# C10450-01.net
KiCad netlist of a schematic drawn in EAGLE
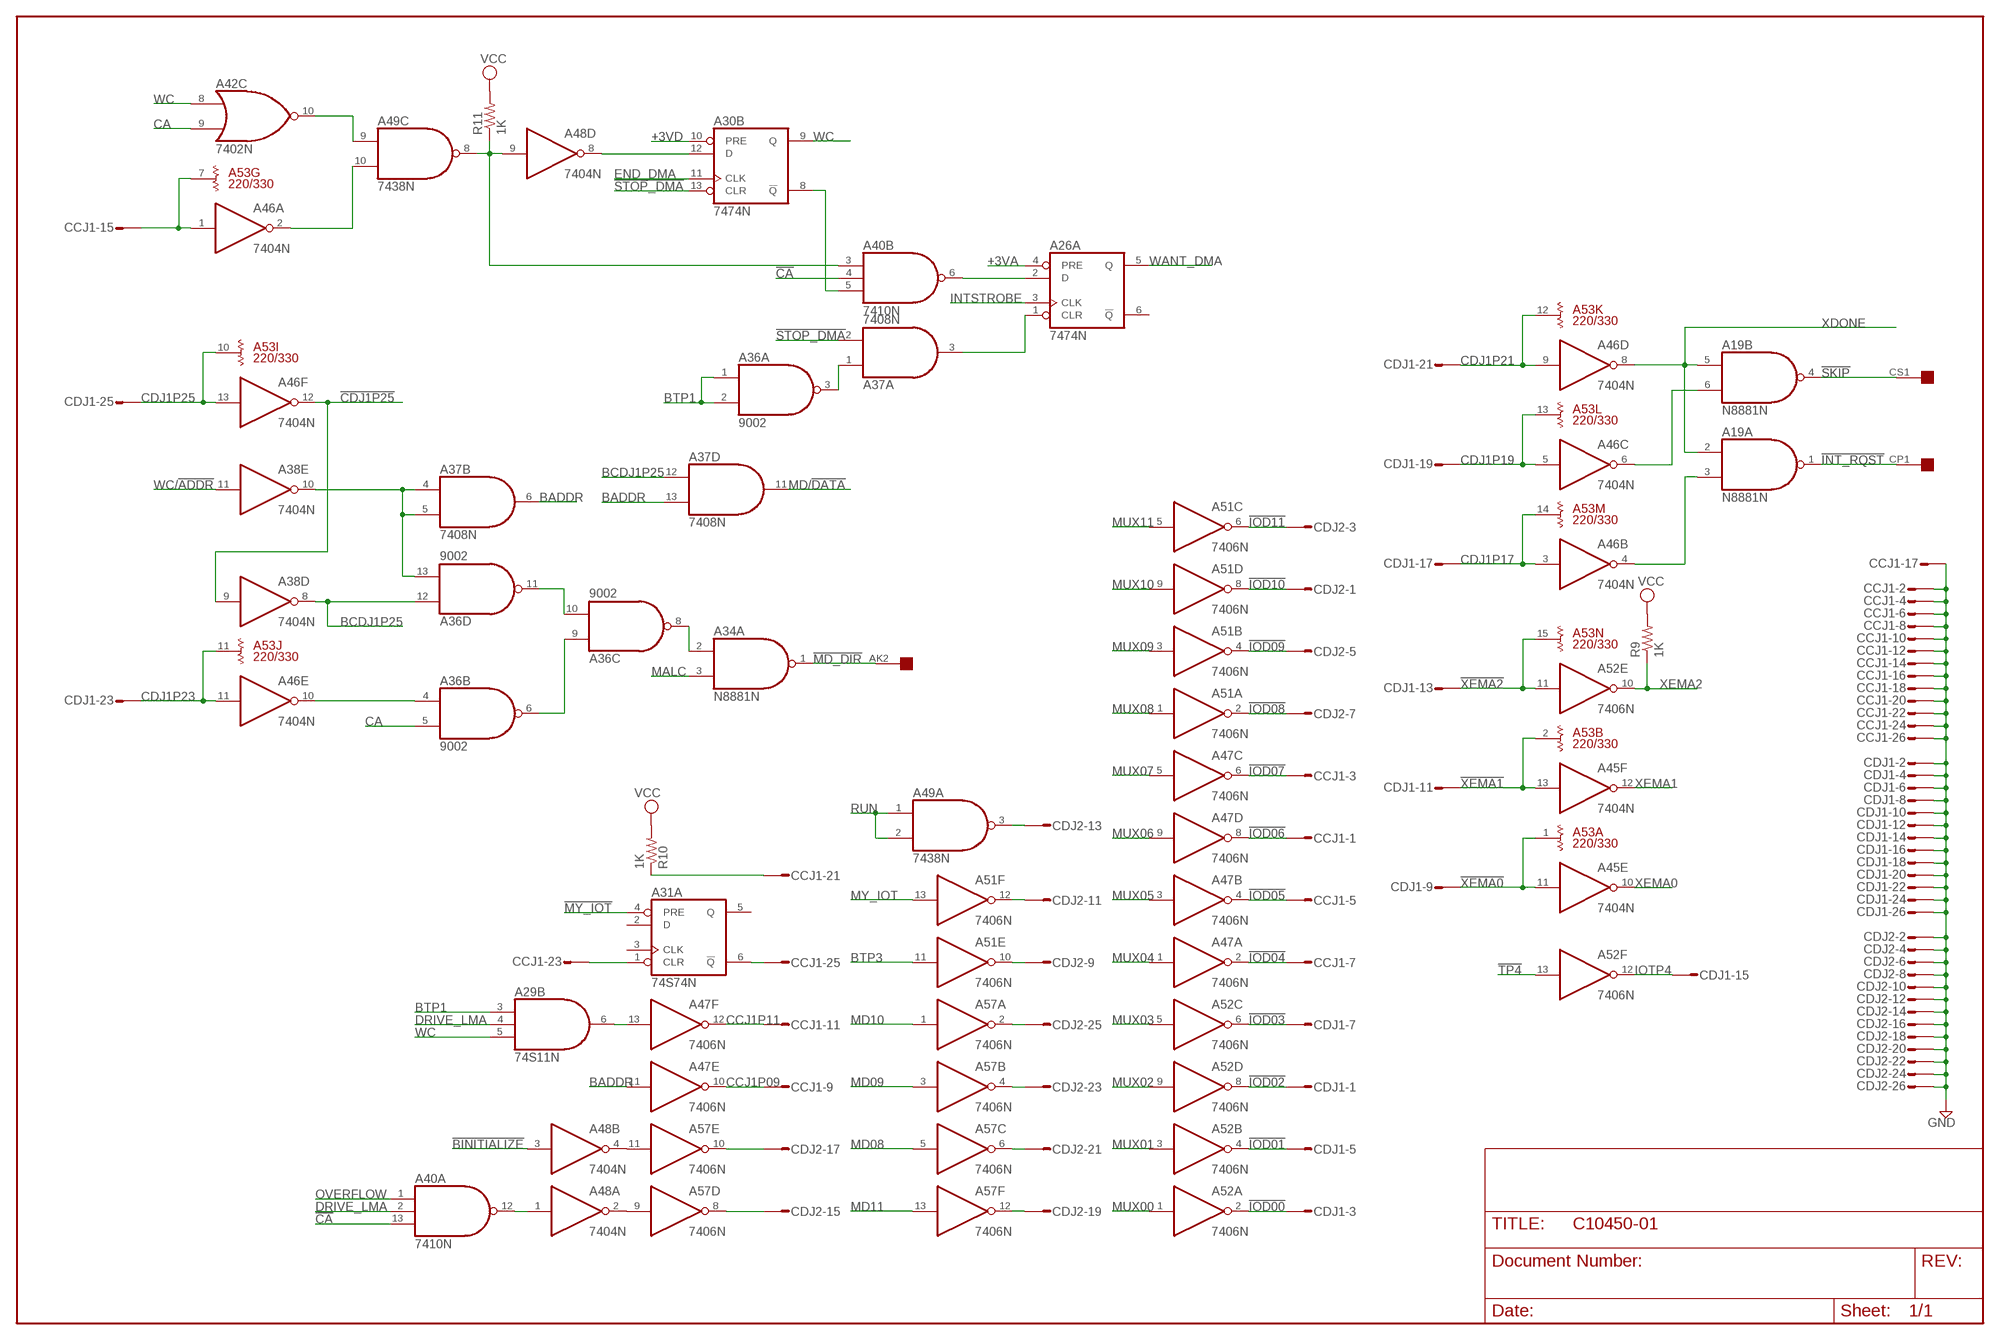
[diagram p0: schematic, sheet 1, part 1 of 3]
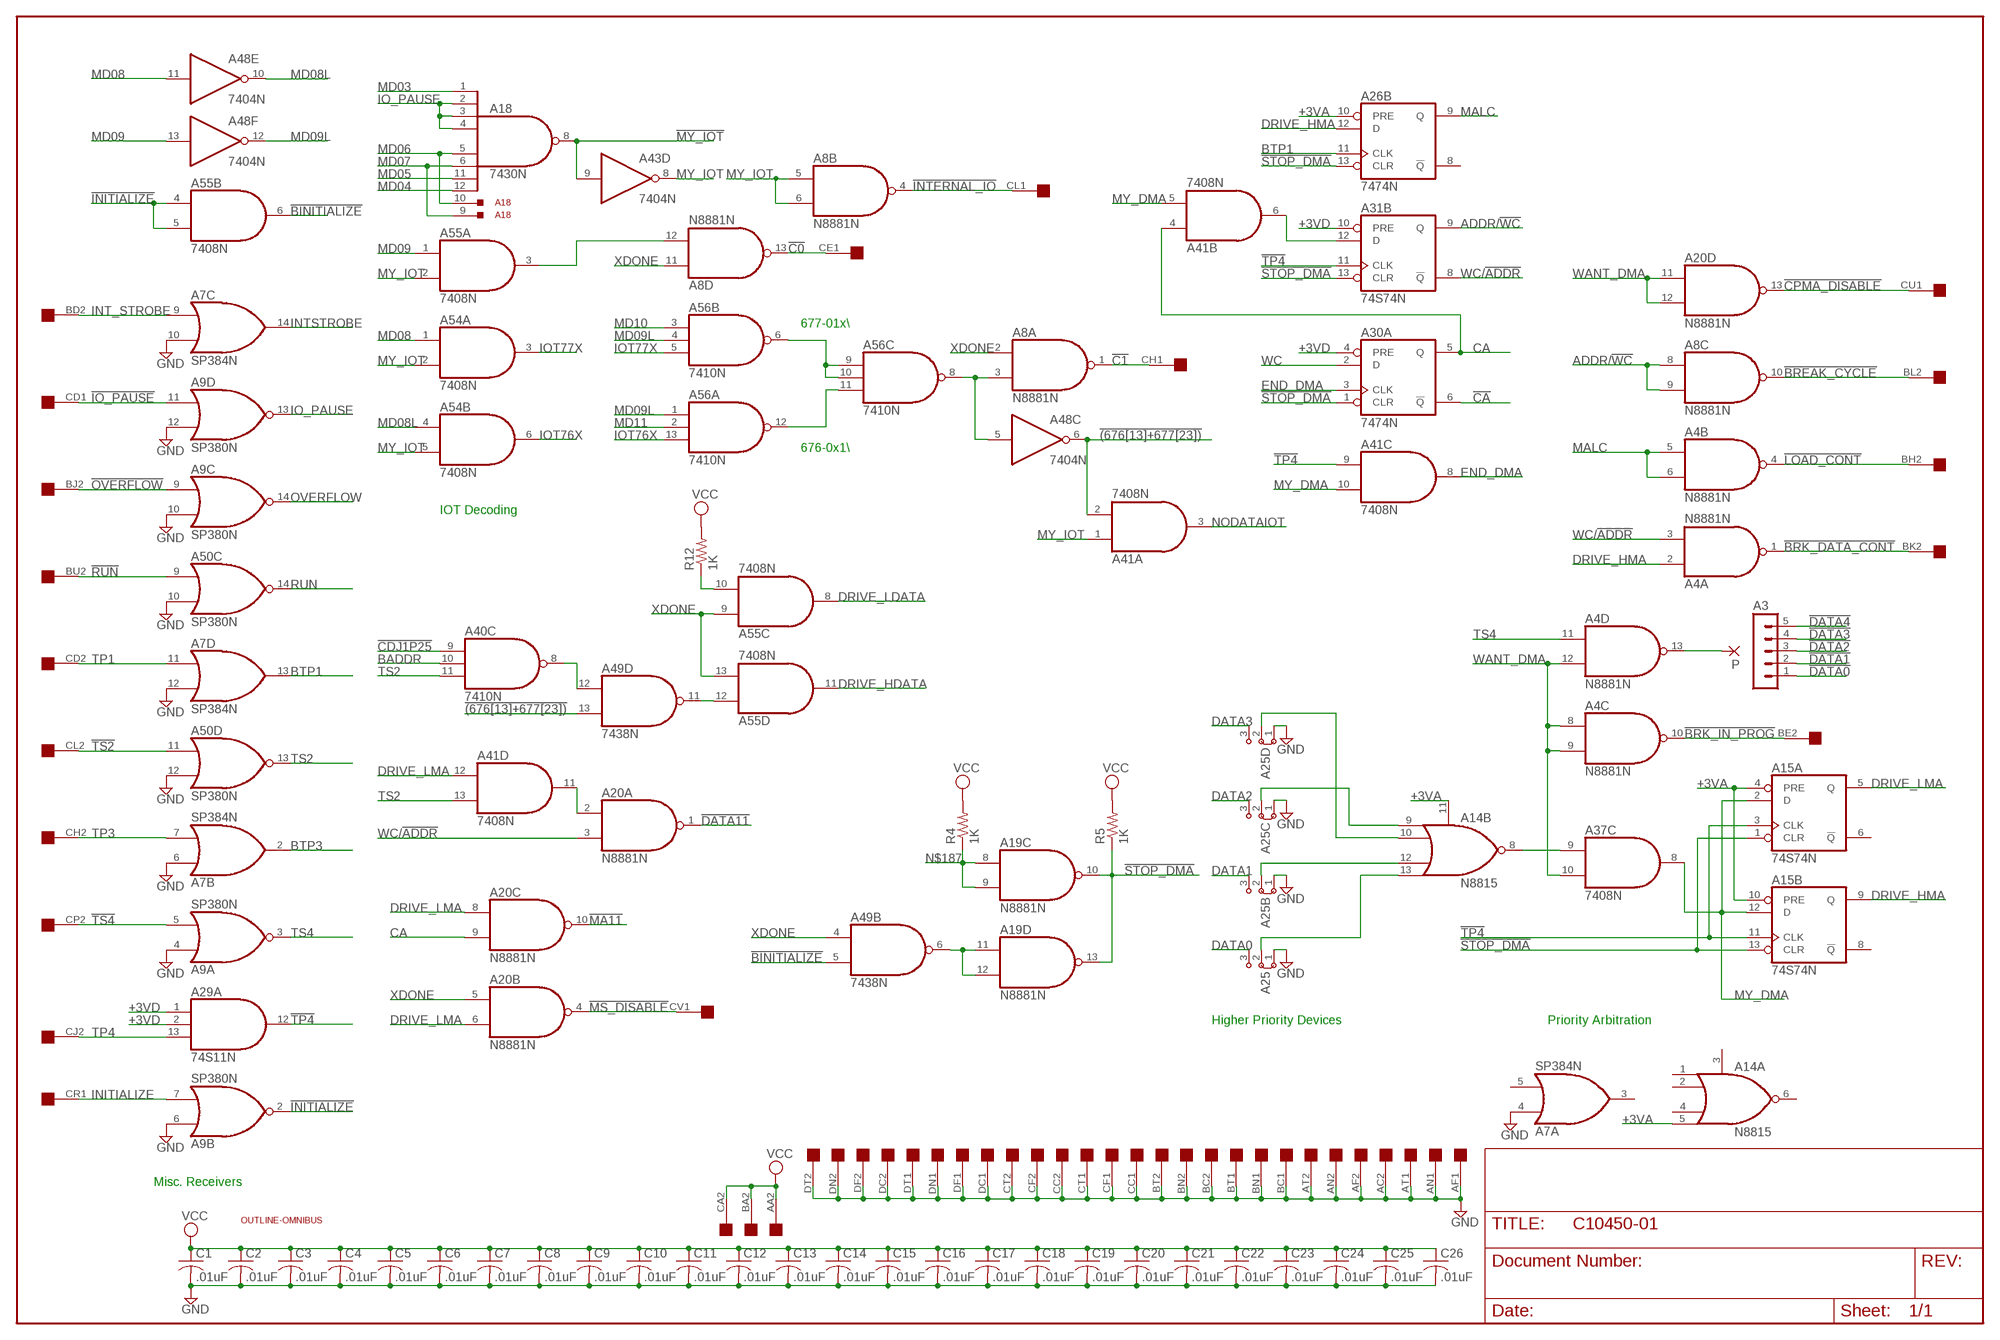
[diagram p1: schematic, sheet 1, part 2 of 3]
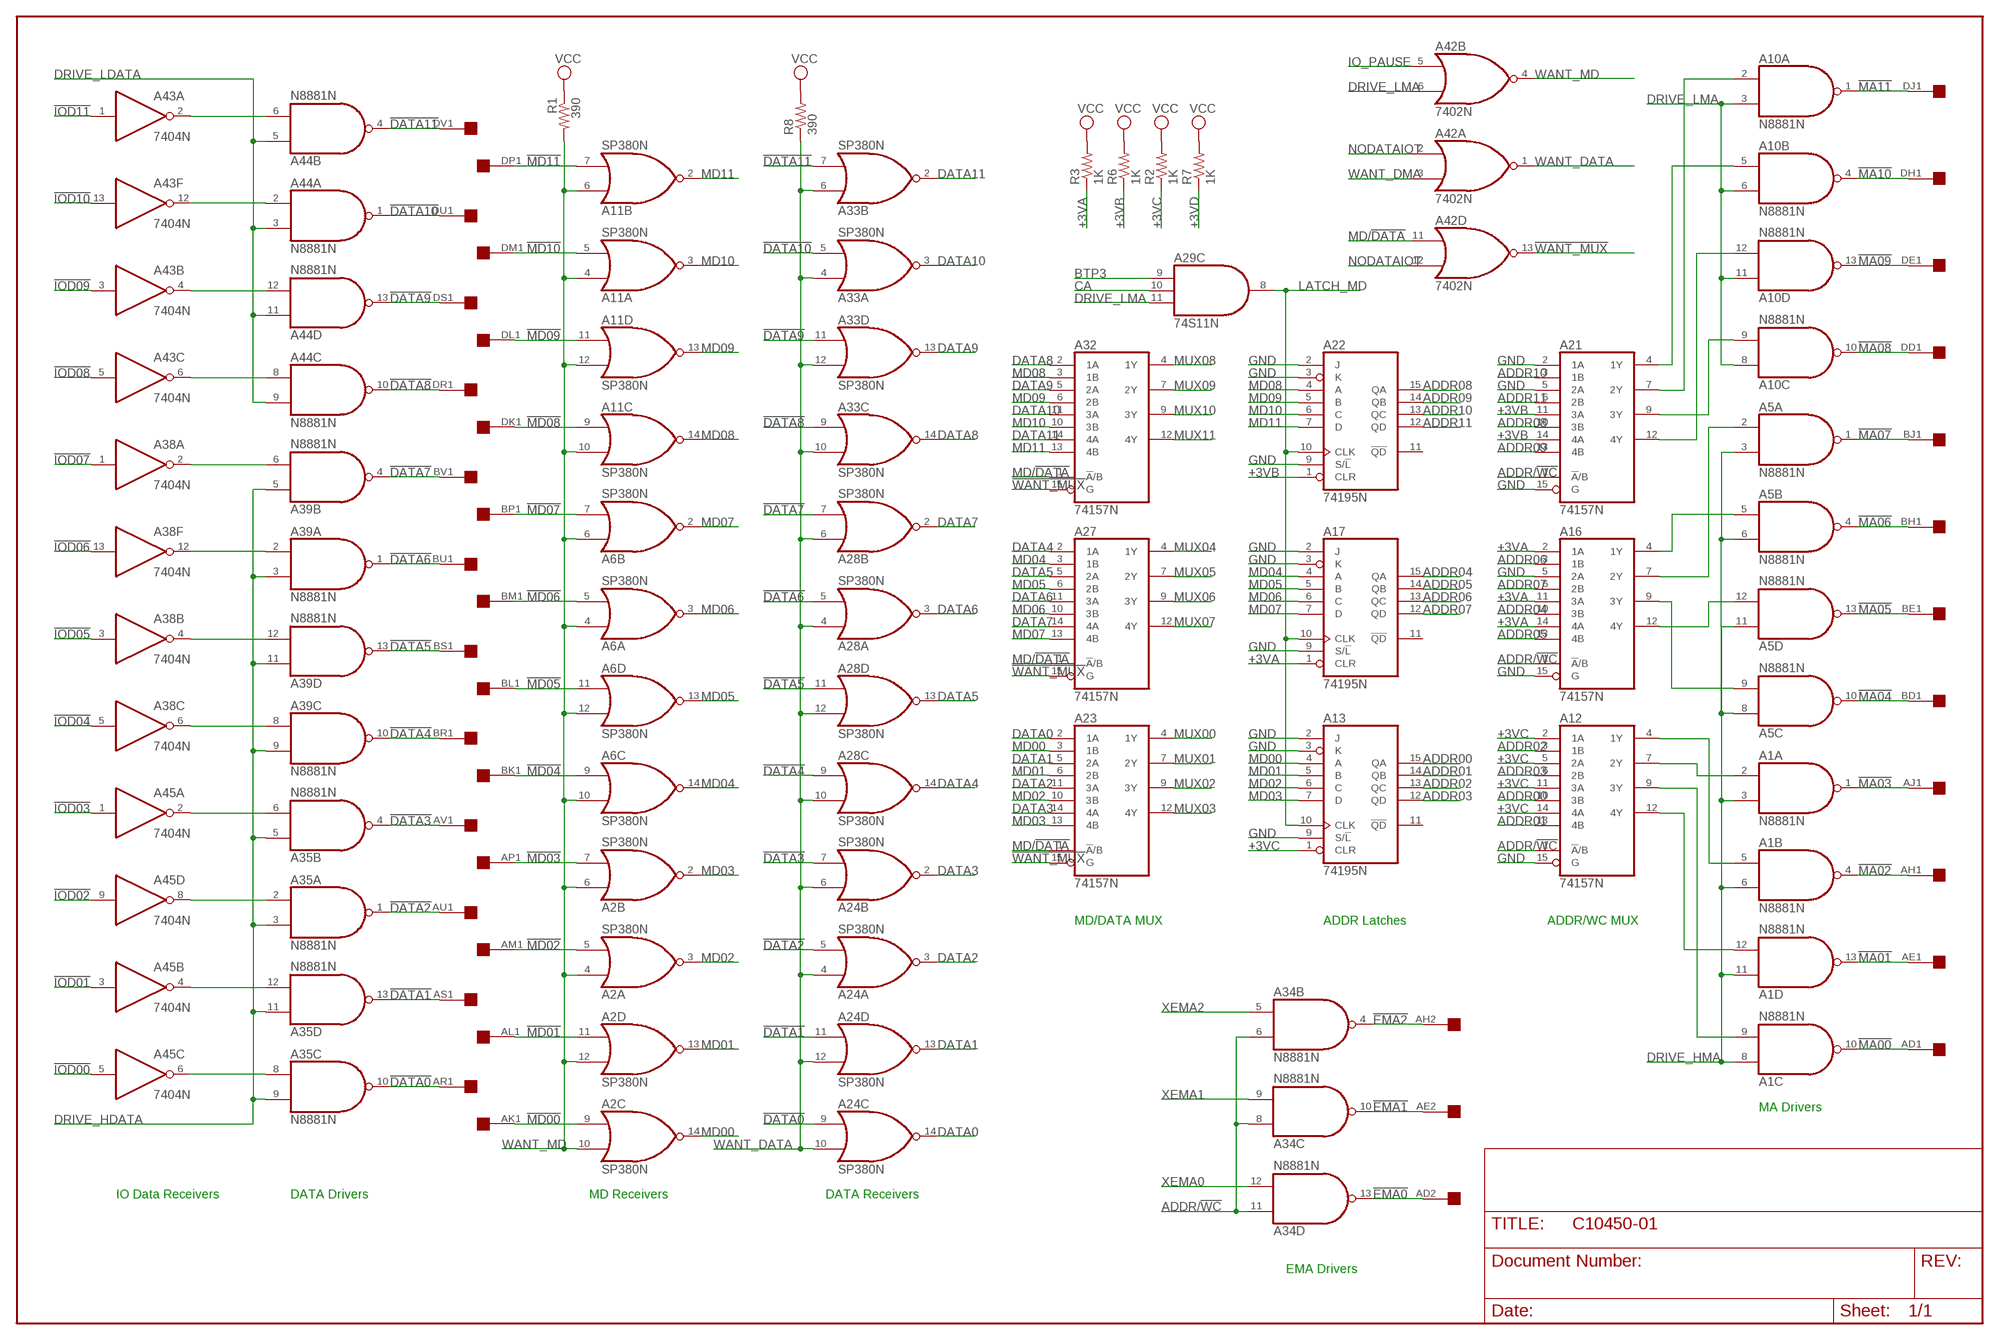
[diagram p2: schematic, sheet 1, part 3 of 3]

(export (version "E")
  (design (tool "Eeschema 10.0.6"))
  (components
    (comp (ref "A1")
      (value "N8881N")
      (footprint "eagle-import:DIL14")
      (libsource (lib "eagle-import") (part "N8881N"))
    )
    (comp (ref "A2")
      (value "SP380N")
      (footprint "eagle-import:DIL14")
      (libsource (lib "eagle-import") (part "SP380N"))
    )
    (comp (ref "A3")
      (value "MA05-1")
      (footprint "eagle-import:MA05-1")
      (libsource (lib "eagle-import") (part "MA05-1"))
    )
    (comp (ref "A4")
      (value "N8881N")
      (footprint "eagle-import:DIL14")
      (libsource (lib "eagle-import") (part "N8881N"))
    )
    (comp (ref "A5")
      (value "N8881N")
      (footprint "eagle-import:DIL14")
      (libsource (lib "eagle-import") (part "N8881N"))
    )
    (comp (ref "A6")
      (value "SP380N")
      (footprint "eagle-import:DIL14")
      (libsource (lib "eagle-import") (part "SP380N"))
    )
    (comp (ref "A7")
      (value "SP384N")
      (footprint "eagle-import:DIL14")
      (libsource (lib "eagle-import") (part "SP384N"))
    )
    (comp (ref "A8")
      (value "N8881N")
      (footprint "eagle-import:DIL14")
      (libsource (lib "eagle-import") (part "N8881N"))
    )
    (comp (ref "A9")
      (value "SP380N")
      (footprint "eagle-import:DIL14")
      (libsource (lib "eagle-import") (part "SP380N"))
    )
    (comp (ref "A10")
      (value "N8881N")
      (footprint "eagle-import:DIL14")
      (libsource (lib "eagle-import") (part "N8881N"))
    )
    (comp (ref "A11")
      (value "SP380N")
      (footprint "eagle-import:DIL14")
      (libsource (lib "eagle-import") (part "SP380N"))
    )
    (comp (ref "A12")
      (value "74157N")
      (footprint "eagle-import:DIL16")
      (libsource (lib "eagle-import") (part "74157N"))
    )
    (comp (ref "A13")
      (value "74195N")
      (footprint "eagle-import:DIL16")
      (libsource (lib "eagle-import") (part "74195NS"))
    )
    (comp (ref "A14")
      (value "N8815")
      (footprint "eagle-import:DIL14")
      (libsource (lib "eagle-import") (part "7425N"))
    )
    (comp (ref "A15")
      (value "74S74N")
      (footprint "eagle-import:DIL14")
      (libsource (lib "eagle-import") (part "7474NS"))
    )
    (comp (ref "A16")
      (value "74157N")
      (footprint "eagle-import:DIL16")
      (libsource (lib "eagle-import") (part "74157N"))
    )
    (comp (ref "A17")
      (value "74195N")
      (footprint "eagle-import:DIL16")
      (libsource (lib "eagle-import") (part "74195NS"))
    )
    (comp (ref "A18")
      (value "7430N")
      (footprint "eagle-import:DIL14")
      (libsource (lib "eagle-import") (part "7430N"))
    )
    (comp (ref "A19")
      (value "N8881N")
      (footprint "eagle-import:DIL14")
      (libsource (lib "eagle-import") (part "N8881N"))
    )
    (comp (ref "A20")
      (value "N8881N")
      (footprint "eagle-import:DIL14")
      (libsource (lib "eagle-import") (part "N8881N"))
    )
    (comp (ref "A21")
      (value "74157N")
      (footprint "eagle-import:DIL16")
      (libsource (lib "eagle-import") (part "74157N"))
    )
    (comp (ref "A22")
      (value "74195N")
      (footprint "eagle-import:DIL16")
      (libsource (lib "eagle-import") (part "74195NS"))
    )
    (comp (ref "A23")
      (value "74157N")
      (footprint "eagle-import:DIL16")
      (libsource (lib "eagle-import") (part "74157N"))
    )
    (comp (ref "A24")
      (value "SP380N")
      (footprint "eagle-import:DIL14")
      (libsource (lib "eagle-import") (part "SP380N"))
    )
    (comp (ref "A25")
      (value "J2X5MM")
      (footprint "eagle-import:05C")
      (libsource (lib "eagle-import") (part "J2X5MM"))
    )
    (comp (ref "A25B")
      (value "J2X5MM")
      (footprint "eagle-import:05C")
      (libsource (lib "eagle-import") (part "J2X5MM"))
    )
    (comp (ref "A25C")
      (value "J2X5MM")
      (footprint "eagle-import:05C")
      (libsource (lib "eagle-import") (part "J2X5MM"))
    )
    (comp (ref "A25D")
      (value "J2X5MM")
      (footprint "eagle-import:05C")
      (libsource (lib "eagle-import") (part "J2X5MM"))
    )
    (comp (ref "A26")
      (value "7474N")
      (footprint "eagle-import:DIL14")
      (libsource (lib "eagle-import") (part "7474NS"))
    )
    (comp (ref "A27")
      (value "74157N")
      (footprint "eagle-import:DIL16")
      (libsource (lib "eagle-import") (part "74157N"))
    )
    (comp (ref "A28")
      (value "SP380N")
      (footprint "eagle-import:DIL14")
      (libsource (lib "eagle-import") (part "SP380N"))
    )
    (comp (ref "A29")
      (value "74S11N")
      (footprint "eagle-import:DIL14")
      (libsource (lib "eagle-import") (part "7411NS"))
    )
    (comp (ref "A30")
      (value "7474N")
      (footprint "eagle-import:DIL14")
      (libsource (lib "eagle-import") (part "7474NS"))
    )
    (comp (ref "A31")
      (value "74S74N")
      (footprint "eagle-import:DIL14")
      (libsource (lib "eagle-import") (part "7474NS"))
    )
    (comp (ref "A32")
      (value "74157N")
      (footprint "eagle-import:DIL16")
      (libsource (lib "eagle-import") (part "74157N"))
    )
    (comp (ref "A33")
      (value "SP380N")
      (footprint "eagle-import:DIL14")
      (libsource (lib "eagle-import") (part "SP380N"))
    )
    (comp (ref "A34")
      (value "N8881N")
      (footprint "eagle-import:DIL14")
      (libsource (lib "eagle-import") (part "N8881N"))
    )
    (comp (ref "A35")
      (value "N8881N")
      (footprint "eagle-import:DIL14")
      (libsource (lib "eagle-import") (part "N8881N"))
    )
    (comp (ref "A36")
      (value "9002")
      (footprint "eagle-import:DIL14")
      (libsource (lib "eagle-import") (part "7400N"))
    )
    (comp (ref "A37")
      (value "7408N")
      (footprint "eagle-import:DIL14")
      (libsource (lib "eagle-import") (part "7408NLS"))
    )
    (comp (ref "A38")
      (value "7404N")
      (footprint "eagle-import:DIL14")
      (libsource (lib "eagle-import") (part "7404N"))
    )
    (comp (ref "A39")
      (value "N8881N")
      (footprint "eagle-import:DIL14")
      (libsource (lib "eagle-import") (part "N8881N"))
    )
    (comp (ref "A40")
      (value "7410N")
      (footprint "eagle-import:DIL14")
      (libsource (lib "eagle-import") (part "7410N"))
    )
    (comp (ref "A41")
      (value "7408N")
      (footprint "eagle-import:DIL14")
      (libsource (lib "eagle-import") (part "7408NLS"))
    )
    (comp (ref "A42")
      (value "7402N")
      (footprint "eagle-import:DIL14")
      (libsource (lib "eagle-import") (part "7402N"))
    )
    (comp (ref "A43")
      (value "7404N")
      (footprint "eagle-import:DIL14")
      (libsource (lib "eagle-import") (part "7404N"))
    )
    (comp (ref "A44")
      (value "N8881N")
      (footprint "eagle-import:DIL14")
      (libsource (lib "eagle-import") (part "N8881N"))
    )
    (comp (ref "A45")
      (value "7404N")
      (footprint "eagle-import:DIL14")
      (libsource (lib "eagle-import") (part "7404N"))
    )
    (comp (ref "A46")
      (value "7404N")
      (footprint "eagle-import:DIL14")
      (libsource (lib "eagle-import") (part "7404N"))
    )
    (comp (ref "A47")
      (value "7406N")
      (footprint "eagle-import:DIL14")
      (libsource (lib "eagle-import") (part "7406N"))
    )
    (comp (ref "A48")
      (value "7404N")
      (footprint "eagle-import:DIL14")
      (libsource (lib "eagle-import") (part "7404N"))
    )
    (comp (ref "A49")
      (value "7438N")
      (footprint "eagle-import:DIL14")
      (libsource (lib "eagle-import") (part "7438N"))
    )
    (comp (ref "A50")
      (value "SP380N")
      (footprint "eagle-import:DIL14")
      (libsource (lib "eagle-import") (part "SP380N"))
    )
    (comp (ref "A51")
      (value "7406N")
      (footprint "eagle-import:DIL14")
      (libsource (lib "eagle-import") (part "7406N"))
    )
    (comp (ref "A52")
      (value "7406N")
      (footprint "eagle-import:DIL14")
      (libsource (lib "eagle-import") (part "7406N"))
    )
    (comp (ref "A53")
      (value "220/330")
      (footprint "eagle-import:DIL16")
      (libsource (lib "eagle-import") (part "220/330"))
    )
    (comp (ref "A54")
      (value "7408N")
      (footprint "eagle-import:DIL14")
      (libsource (lib "eagle-import") (part "7408NLS"))
    )
    (comp (ref "A55")
      (value "7408N")
      (footprint "eagle-import:DIL14")
      (libsource (lib "eagle-import") (part "7408NLS"))
    )
    (comp (ref "A56")
      (value "7410N")
      (footprint "eagle-import:DIL14")
      (libsource (lib "eagle-import") (part "7410N"))
    )
    (comp (ref "A57")
      (value "7406N")
      (footprint "eagle-import:DIL14")
      (libsource (lib "eagle-import") (part "7406N"))
    )
    (comp (ref "C1")
      (value ".01uF")
      (footprint "eagle-import:C050-025X075")
      (libsource (lib "eagle-import") (part "C-US050-025X075"))
    )
    (comp (ref "C2")
      (value ".01uF")
      (footprint "eagle-import:C050-025X075")
      (libsource (lib "eagle-import") (part "C-US050-025X075"))
    )
    (comp (ref "C3")
      (value ".01uF")
      (footprint "eagle-import:C050-025X075")
      (libsource (lib "eagle-import") (part "C-US050-025X075"))
    )
    (comp (ref "C4")
      (value ".01uF")
      (footprint "eagle-import:C050-025X075")
      (libsource (lib "eagle-import") (part "C-US050-025X075"))
    )
    (comp (ref "C5")
      (value ".01uF")
      (footprint "eagle-import:C050-025X075")
      (libsource (lib "eagle-import") (part "C-US050-025X075"))
    )
    (comp (ref "C6")
      (value ".01uF")
      (footprint "eagle-import:C050-025X075")
      (libsource (lib "eagle-import") (part "C-US050-025X075"))
    )
    (comp (ref "C7")
      (value ".01uF")
      (footprint "eagle-import:C050-025X075")
      (libsource (lib "eagle-import") (part "C-US050-025X075"))
    )
    (comp (ref "C8")
      (value ".01uF")
      (footprint "eagle-import:C050-025X075")
      (libsource (lib "eagle-import") (part "C-US050-025X075"))
    )
    (comp (ref "C9")
      (value ".01uF")
      (footprint "eagle-import:C050-025X075")
      (libsource (lib "eagle-import") (part "C-US050-025X075"))
    )
    (comp (ref "C10")
      (value ".01uF")
      (footprint "eagle-import:C050-025X075")
      (libsource (lib "eagle-import") (part "C-US050-025X075"))
    )
    (comp (ref "C11")
      (value ".01uF")
      (footprint "eagle-import:C050-025X075")
      (libsource (lib "eagle-import") (part "C-US050-025X075"))
    )
    (comp (ref "C12")
      (value ".01uF")
      (footprint "eagle-import:C050-025X075")
      (libsource (lib "eagle-import") (part "C-US050-025X075"))
    )
    (comp (ref "C13")
      (value ".01uF")
      (footprint "eagle-import:C050-025X075")
      (libsource (lib "eagle-import") (part "C-US050-025X075"))
    )
    (comp (ref "C14")
      (value ".01uF")
      (footprint "eagle-import:C050-025X075")
      (libsource (lib "eagle-import") (part "C-US050-025X075"))
    )
    (comp (ref "C15")
      (value ".01uF")
      (footprint "eagle-import:C050-025X075")
      (libsource (lib "eagle-import") (part "C-US050-025X075"))
    )
    (comp (ref "C16")
      (value ".01uF")
      (footprint "eagle-import:C050-025X075")
      (libsource (lib "eagle-import") (part "C-US050-025X075"))
    )
    (comp (ref "C17")
      (value ".01uF")
      (footprint "eagle-import:C050-025X075")
      (libsource (lib "eagle-import") (part "C-US050-025X075"))
    )
    (comp (ref "C18")
      (value ".01uF")
      (footprint "eagle-import:C050-025X075")
      (libsource (lib "eagle-import") (part "C-US050-025X075"))
    )
    (comp (ref "C19")
      (value ".01uF")
      (footprint "eagle-import:C050-025X075")
      (libsource (lib "eagle-import") (part "C-US050-025X075"))
    )
    (comp (ref "C20")
      (value ".01uF")
      (footprint "eagle-import:C050-025X075")
      (libsource (lib "eagle-import") (part "C-US050-025X075"))
    )
    (comp (ref "C21")
      (value ".01uF")
      (footprint "eagle-import:C050-025X075")
      (libsource (lib "eagle-import") (part "C-US050-025X075"))
    )
    (comp (ref "C22")
      (value ".01uF")
      (footprint "eagle-import:C050-025X075")
      (libsource (lib "eagle-import") (part "C-US050-025X075"))
    )
    (comp (ref "C23")
      (value ".01uF")
      (footprint "eagle-import:C050-025X075")
      (libsource (lib "eagle-import") (part "C-US050-025X075"))
    )
    (comp (ref "C24")
      (value ".01uF")
      (footprint "eagle-import:C050-025X075")
      (libsource (lib "eagle-import") (part "C-US050-025X075"))
    )
    (comp (ref "C25")
      (value ".01uF")
      (footprint "eagle-import:C050-025X075")
      (libsource (lib "eagle-import") (part "C-US050-025X075"))
    )
    (comp (ref "C26")
      (value ".01uF")
      (footprint "eagle-import:C050-025X075")
      (libsource (lib "eagle-import") (part "C-US050-025X075"))
    )
    (comp (ref "CCJ1")
      (value "26HS")
      (footprint "eagle-import:26H")
      (libsource (lib "eagle-import") (part "26HS"))
    )
    (comp (ref "CDJ1")
      (value "26HS")
      (footprint "eagle-import:26H")
      (libsource (lib "eagle-import") (part "26HS"))
    )
    (comp (ref "CDJ2")
      (value "26HS")
      (footprint "eagle-import:26H")
      (libsource (lib "eagle-import") (part "26HS"))
    )
    (comp (ref "P")
      (value "1,6/0,8")
      (footprint "eagle-import:1,6_0,8")
      (libsource (lib "eagle-import") (part "1,6/0,8"))
    )
    (comp (ref "R1")
      (value "390")
      (footprint "eagle-import:0207_10")
      (libsource (lib "eagle-import") (part "R-US_0207/10"))
    )
    (comp (ref "R2")
      (value "1K")
      (footprint "eagle-import:0207_10")
      (libsource (lib "eagle-import") (part "R-US_0207/10"))
    )
    (comp (ref "R3")
      (value "1K")
      (footprint "eagle-import:0207_10")
      (libsource (lib "eagle-import") (part "R-US_0207/10"))
    )
    (comp (ref "R4")
      (value "1K")
      (footprint "eagle-import:0207_10")
      (libsource (lib "eagle-import") (part "R-US_0207/10"))
    )
    (comp (ref "R5")
      (value "1K")
      (footprint "eagle-import:0207_10")
      (libsource (lib "eagle-import") (part "R-US_0207/10"))
    )
    (comp (ref "R6")
      (value "1K")
      (footprint "eagle-import:0207_10")
      (libsource (lib "eagle-import") (part "R-US_0207/10"))
    )
    (comp (ref "R7")
      (value "1K")
      (footprint "eagle-import:0207_10")
      (libsource (lib "eagle-import") (part "R-US_0207/10"))
    )
    (comp (ref "R8")
      (value "390")
      (footprint "eagle-import:0207_10")
      (libsource (lib "eagle-import") (part "R-US_0207/10"))
    )
    (comp (ref "R9")
      (value "1K")
      (footprint "eagle-import:0207_10")
      (libsource (lib "eagle-import") (part "R-US_0207/10"))
    )
    (comp (ref "R10")
      (value "1K")
      (footprint "eagle-import:0207_10")
      (libsource (lib "eagle-import") (part "R-US_0207/10"))
    )
    (comp (ref "R11")
      (value "1K")
      (footprint "eagle-import:0207_10")
      (libsource (lib "eagle-import") (part "R-US_0207/10"))
    )
    (comp (ref "R12")
      (value "1K")
      (footprint "eagle-import:0207_10")
      (libsource (lib "eagle-import") (part "R-US_0207/10"))
    )
    (comp (ref "U$1")
      (value "OUTLINE-OMNIBUS")
      (footprint "eagle-import:OMNIBUS")
      (libsource (lib "eagle-import") (part "OUTLINE-OMNIBUS"))
    )
    (comp (ref "U$2")
      (value "QUAD")
      (footprint "eagle-import:EDGE-CON8")
      (libsource (lib "eagle-import") (part "QUAD"))
    )
  )
  (nets
    (net (code "1") (name "/+3VA") (class "Default")
      (node (ref "A14") (pin "11") (pinfunction "G_11") (pintype "input"))
      (node (ref "A14") (pin "5") (pinfunction "I3_5") (pintype "input"))
      (node (ref "A15") (pin "10") (pinfunction "PRE_10") (pintype "input"))
      (node (ref "A15") (pin "4") (pinfunction "PRE_4") (pintype "input"))
      (node (ref "A16") (pin "11") (pinfunction "3A_11") (pintype "input"))
      (node (ref "A16") (pin "14") (pinfunction "4A_14") (pintype "input"))
      (node (ref "A16") (pin "2") (pinfunction "1A_2") (pintype "input"))
      (node (ref "A17") (pin "1") (pinfunction "CLR_1") (pintype "input"))
      (node (ref "A26") (pin "10") (pinfunction "PRE_10") (pintype "input"))
      (node (ref "A26") (pin "4") (pinfunction "PRE_4") (pintype "input"))
      (node (ref "R3") (pin "1") (pinfunction "1_1") (pintype "passive"))
    )
    (net (code "2") (name "/+3VB") (class "Default")
      (node (ref "A21") (pin "11") (pinfunction "3A_11") (pintype "input"))
      (node (ref "A21") (pin "14") (pinfunction "4A_14") (pintype "input"))
      (node (ref "A22") (pin "1") (pinfunction "CLR_1") (pintype "input"))
      (node (ref "R6") (pin "1") (pinfunction "1_1") (pintype "passive"))
    )
    (net (code "3") (name "/+3VC") (class "Default")
      (node (ref "A12") (pin "11") (pinfunction "3A_11") (pintype "input"))
      (node (ref "A12") (pin "14") (pinfunction "4A_14") (pintype "input"))
      (node (ref "A12") (pin "2") (pinfunction "1A_2") (pintype "input"))
      (node (ref "A12") (pin "5") (pinfunction "2A_5") (pintype "input"))
      (node (ref "A13") (pin "1") (pinfunction "CLR_1") (pintype "input"))
      (node (ref "R2") (pin "1") (pinfunction "1_1") (pintype "passive"))
    )
    (net (code "4") (name "/+3VD") (class "Default")
      (node (ref "A29") (pin "1") (pinfunction "I0_1") (pintype "input"))
      (node (ref "A29") (pin "2") (pinfunction "I1_2") (pintype "input"))
      (node (ref "A30") (pin "10") (pinfunction "PRE_10") (pintype "input"))
      (node (ref "A30") (pin "4") (pinfunction "PRE_4") (pintype "input"))
      (node (ref "A31") (pin "10") (pinfunction "PRE_10") (pintype "input"))
      (node (ref "R7") (pin "1") (pinfunction "1_1") (pintype "passive"))
    )
    (net (code "5") (name "/ADDR00") (class "Default")
      (node (ref "A12") (pin "10") (pinfunction "3B_10") (pintype "input"))
      (node (ref "A13") (pin "15") (pinfunction "QA_15") (pintype "output"))
    )
    (net (code "6") (name "/ADDR01") (class "Default")
      (node (ref "A12") (pin "13") (pinfunction "4B_13") (pintype "input"))
      (node (ref "A13") (pin "14") (pinfunction "QB_14") (pintype "output"))
    )
    (net (code "7") (name "/ADDR02") (class "Default")
      (node (ref "A12") (pin "3") (pinfunction "1B_3") (pintype "input"))
      (node (ref "A13") (pin "13") (pinfunction "QC_13") (pintype "output"))
    )
    (net (code "8") (name "/ADDR03") (class "Default")
      (node (ref "A12") (pin "6") (pinfunction "2B_6") (pintype "input"))
      (node (ref "A13") (pin "12") (pinfunction "QD_12") (pintype "output"))
    )
    (net (code "9") (name "/ADDR04") (class "Default")
      (node (ref "A16") (pin "10") (pinfunction "3B_10") (pintype "input"))
      (node (ref "A17") (pin "15") (pinfunction "QA_15") (pintype "output"))
    )
    (net (code "10") (name "/ADDR05") (class "Default")
      (node (ref "A16") (pin "13") (pinfunction "4B_13") (pintype "input"))
      (node (ref "A17") (pin "14") (pinfunction "QB_14") (pintype "output"))
    )
    (net (code "11") (name "/ADDR06") (class "Default")
      (node (ref "A16") (pin "3") (pinfunction "1B_3") (pintype "input"))
      (node (ref "A17") (pin "13") (pinfunction "QC_13") (pintype "output"))
    )
    (net (code "12") (name "/ADDR07") (class "Default")
      (node (ref "A16") (pin "6") (pinfunction "2B_6") (pintype "input"))
      (node (ref "A17") (pin "12") (pinfunction "QD_12") (pintype "output"))
    )
    (net (code "13") (name "/ADDR08") (class "Default")
      (node (ref "A21") (pin "10") (pinfunction "3B_10") (pintype "input"))
      (node (ref "A22") (pin "15") (pinfunction "QA_15") (pintype "output"))
    )
    (net (code "14") (name "/ADDR09") (class "Default")
      (node (ref "A21") (pin "13") (pinfunction "4B_13") (pintype "input"))
      (node (ref "A22") (pin "14") (pinfunction "QB_14") (pintype "output"))
    )
    (net (code "15") (name "/ADDR10") (class "Default")
      (node (ref "A21") (pin "3") (pinfunction "1B_3") (pintype "input"))
      (node (ref "A22") (pin "13") (pinfunction "QC_13") (pintype "output"))
    )
    (net (code "16") (name "/ADDR11") (class "Default")
      (node (ref "A21") (pin "6") (pinfunction "2B_6") (pintype "input"))
      (node (ref "A22") (pin "12") (pinfunction "QD_12") (pintype "output"))
    )
    (net (code "17") (name "/ADDR{slash}~{WC}") (class "Default")
      (node (ref "A12") (pin "1") (pinfunction "~{A}/B_1") (pintype "input"))
      (node (ref "A16") (pin "1") (pinfunction "~{A}/B_1") (pintype "input"))
      (node (ref "A21") (pin "1") (pinfunction "~{A}/B_1") (pintype "input"))
      (node (ref "A31") (pin "9") (pinfunction "Q_9") (pintype "output"))
      (node (ref "A34") (pin "11") (pinfunction "I0_11") (pintype "input"))
      (node (ref "A34") (pin "6") (pinfunction "I1_6") (pintype "input"))
      (node (ref "A34") (pin "8") (pinfunction "I0_8") (pintype "input"))
      (node (ref "A8") (pin "8") (pinfunction "I0_8") (pintype "input"))
      (node (ref "A8") (pin "9") (pinfunction "I1_9") (pintype "input"))
    )
    (net (code "18") (name "/BADDR") (class "Default")
      (node (ref "A37") (pin "13") (pinfunction "I1_13") (pintype "input"))
      (node (ref "A37") (pin "6") (pinfunction "O_6") (pintype "output"))
      (node (ref "A40") (pin "10") (pinfunction "I1_10") (pintype "input"))
      (node (ref "A47") (pin "11") (pinfunction "I_11") (pintype "input"))
    )
    (net (code "19") (name "/BCDJ1P25") (class "Default")
      (node (ref "A36") (pin "12") (pinfunction "I0_12") (pintype "input"))
      (node (ref "A37") (pin "12") (pinfunction "I0_12") (pintype "input"))
      (node (ref "A38") (pin "8") (pinfunction "O_8") (pintype "output"))
    )
    (net (code "20") (name "/BTP1") (class "Default")
      (node (ref "A26") (pin "11") (pinfunction "CLK_11") (pintype "input"))
      (node (ref "A29") (pin "3") (pinfunction "I0_3") (pintype "input"))
      (node (ref "A36") (pin "1") (pinfunction "I0_1") (pintype "input"))
      (node (ref "A36") (pin "2") (pinfunction "I1_2") (pintype "input"))
      (node (ref "A7") (pin "13") (pinfunction "O_13") (pintype "output"))
    )
    (net (code "21") (name "/BTP3") (class "Default")
      (node (ref "A29") (pin "9") (pinfunction "I0_9") (pintype "input"))
      (node (ref "A51") (pin "11") (pinfunction "I_11") (pintype "input"))
      (node (ref "A7") (pin "2") (pinfunction "O_2") (pintype "output"))
    )
    (net (code "22") (name "/CA") (class "Default")
      (node (ref "A20") (pin "9") (pinfunction "I1_9") (pintype "input"))
      (node (ref "A29") (pin "10") (pinfunction "I1_10") (pintype "input"))
      (node (ref "A30") (pin "5") (pinfunction "Q_5") (pintype "output"))
      (node (ref "A36") (pin "5") (pinfunction "I1_5") (pintype "input"))
      (node (ref "A41") (pin "4") (pinfunction "I0_4") (pintype "input"))
      (node (ref "A42") (pin "9") (pinfunction "I1_9") (pintype "input"))
    )
    (net (code "23") (name "/CCJ1P09") (class "Default")
      (node (ref "A47") (pin "10") (pinfunction "O_10") (pintype "open_collector"))
      (node (ref "CCJ1") (pin "9") (pinfunction "S_9") (pintype "passive"))
    )
    (net (code "24") (name "/CCJ1P11") (class "Default")
      (node (ref "A47") (pin "12") (pinfunction "O_12") (pintype "open_collector"))
      (node (ref "CCJ1") (pin "11") (pinfunction "S_11") (pintype "passive"))
    )
    (net (code "25") (name "/CDJ1P17") (class "Default")
      (node (ref "A46") (pin "3") (pinfunction "I_3") (pintype "input"))
      (node (ref "A53") (pin "14") (pinfunction "TERM_14") (pintype "input"))
      (node (ref "CDJ1") (pin "17") (pinfunction "S_17") (pintype "passive"))
    )
    (net (code "26") (name "/CDJ1P19") (class "Default")
      (node (ref "A46") (pin "5") (pinfunction "I_5") (pintype "input"))
      (node (ref "A53") (pin "13") (pinfunction "TERM_13") (pintype "input"))
      (node (ref "CDJ1") (pin "19") (pinfunction "S_19") (pintype "passive"))
    )
    (net (code "27") (name "/CDJ1P21") (class "Default")
      (node (ref "A46") (pin "9") (pinfunction "I_9") (pintype "input"))
      (node (ref "A53") (pin "12") (pinfunction "TERM_12") (pintype "input"))
      (node (ref "CDJ1") (pin "21") (pinfunction "S_21") (pintype "passive"))
    )
    (net (code "28") (name "/CDJ1P23") (class "Default")
      (node (ref "A46") (pin "11") (pinfunction "I_11") (pintype "input"))
      (node (ref "A53") (pin "11") (pinfunction "TERM_11") (pintype "input"))
      (node (ref "CDJ1") (pin "23") (pinfunction "S_23") (pintype "passive"))
    )
    (net (code "29") (name "/CDJ1P25") (class "Default")
      (node (ref "A46") (pin "13") (pinfunction "I_13") (pintype "input"))
      (node (ref "A53") (pin "10") (pinfunction "TERM_10") (pintype "input"))
      (node (ref "CDJ1") (pin "25") (pinfunction "S_25") (pintype "passive"))
    )
    (net (code "30") (name "/DATA0") (class "Default")
      (node (ref "A23") (pin "2") (pinfunction "1A_2") (pintype "input"))
      (node (ref "A24") (pin "14") (pinfunction "O_14") (pintype "output"))
      (node (ref "A25") (pin "3") (pinfunction "3_3") (pintype "passive"))
    )
    (net (code "31") (name "/DATA1") (class "Default")
      (node (ref "A23") (pin "5") (pinfunction "2A_5") (pintype "input"))
      (node (ref "A24") (pin "13") (pinfunction "O_13") (pintype "output"))
      (node (ref "A25B") (pin "3") (pinfunction "3_3") (pintype "passive"))
    )
    (net (code "32") (name "/DATA2") (class "Default")
      (node (ref "A23") (pin "11") (pinfunction "3A_11") (pintype "input"))
      (node (ref "A24") (pin "3") (pinfunction "O_3") (pintype "output"))
      (node (ref "A25C") (pin "3") (pinfunction "3_3") (pintype "passive"))
    )
    (net (code "33") (name "/DATA3") (class "Default")
      (node (ref "A23") (pin "14") (pinfunction "4A_14") (pintype "input"))
      (node (ref "A24") (pin "2") (pinfunction "O_2") (pintype "output"))
      (node (ref "A25D") (pin "3") (pinfunction "3_3") (pintype "passive"))
    )
    (net (code "34") (name "/DATA4") (class "Default")
      (node (ref "A27") (pin "2") (pinfunction "1A_2") (pintype "input"))
      (node (ref "A28") (pin "14") (pinfunction "O_14") (pintype "output"))
    )
    (net (code "35") (name "/DATA5") (class "Default")
      (node (ref "A27") (pin "5") (pinfunction "2A_5") (pintype "input"))
      (node (ref "A28") (pin "13") (pinfunction "O_13") (pintype "output"))
    )
    (net (code "36") (name "/DATA6") (class "Default")
      (node (ref "A27") (pin "11") (pinfunction "3A_11") (pintype "input"))
      (node (ref "A28") (pin "3") (pinfunction "O_3") (pintype "output"))
    )
    (net (code "37") (name "/DATA7") (class "Default")
      (node (ref "A27") (pin "14") (pinfunction "4A_14") (pintype "input"))
      (node (ref "A28") (pin "2") (pinfunction "O_2") (pintype "output"))
    )
    (net (code "38") (name "/DATA8") (class "Default")
      (node (ref "A32") (pin "2") (pinfunction "1A_2") (pintype "input"))
      (node (ref "A33") (pin "14") (pinfunction "O_14") (pintype "output"))
    )
    (net (code "39") (name "/DATA9") (class "Default")
      (node (ref "A32") (pin "5") (pinfunction "2A_5") (pintype "input"))
      (node (ref "A33") (pin "13") (pinfunction "O_13") (pintype "output"))
    )
    (net (code "40") (name "/DATA10") (class "Default")
      (node (ref "A32") (pin "11") (pinfunction "3A_11") (pintype "input"))
      (node (ref "A33") (pin "3") (pinfunction "O_3") (pintype "output"))
    )
    (net (code "41") (name "/DATA11") (class "Default")
      (node (ref "A32") (pin "14") (pinfunction "4A_14") (pintype "input"))
      (node (ref "A33") (pin "2") (pinfunction "O_2") (pintype "output"))
    )
    (net (code "42") (name "/DRIVE_HDATA") (class "Default")
      (node (ref "A35") (pin "11") (pinfunction "I0_11") (pintype "input"))
      (node (ref "A35") (pin "3") (pinfunction "I1_3") (pintype "input"))
      (node (ref "A35") (pin "5") (pinfunction "I0_5") (pintype "input"))
      (node (ref "A35") (pin "9") (pinfunction "I1_9") (pintype "input"))
      (node (ref "A39") (pin "11") (pinfunction "I0_11") (pintype "input"))
      (node (ref "A39") (pin "3") (pinfunction "I1_3") (pintype "input"))
      (node (ref "A39") (pin "5") (pinfunction "I0_5") (pintype "input"))
      (node (ref "A39") (pin "9") (pinfunction "I1_9") (pintype "input"))
      (node (ref "A55") (pin "11") (pinfunction "O_11") (pintype "output"))
    )
    (net (code "43") (name "/DRIVE_HMA") (class "Default")
      (node (ref "A1") (pin "11") (pinfunction "I0_11") (pintype "input"))
      (node (ref "A1") (pin "3") (pinfunction "I1_3") (pintype "input"))
      (node (ref "A1") (pin "6") (pinfunction "I1_6") (pintype "input"))
      (node (ref "A1") (pin "8") (pinfunction "I0_8") (pintype "input"))
      (node (ref "A15") (pin "9") (pinfunction "Q_9") (pintype "output"))
      (node (ref "A26") (pin "12") (pinfunction "D_12") (pintype "input"))
      (node (ref "A4") (pin "2") (pinfunction "I0_2") (pintype "input"))
      (node (ref "A5") (pin "11") (pinfunction "I0_11") (pintype "input"))
      (node (ref "A5") (pin "3") (pinfunction "I1_3") (pintype "input"))
      (node (ref "A5") (pin "6") (pinfunction "I1_6") (pintype "input"))
      (node (ref "A5") (pin "8") (pinfunction "I0_8") (pintype "input"))
    )
    (net (code "44") (name "/DRIVE_LDATA") (class "Default")
      (node (ref "A44") (pin "11") (pinfunction "I0_11") (pintype "input"))
      (node (ref "A44") (pin "3") (pinfunction "I1_3") (pintype "input"))
      (node (ref "A44") (pin "5") (pinfunction "I0_5") (pintype "input"))
      (node (ref "A44") (pin "9") (pinfunction "I1_9") (pintype "input"))
      (node (ref "A55") (pin "8") (pinfunction "O_8") (pintype "output"))
    )
    (net (code "45") (name "/DRIVE_LMA") (class "Default")
      (node (ref "A10") (pin "11") (pinfunction "I0_11") (pintype "input"))
      (node (ref "A10") (pin "3") (pinfunction "I1_3") (pintype "input"))
      (node (ref "A10") (pin "6") (pinfunction "I1_6") (pintype "input"))
      (node (ref "A10") (pin "8") (pinfunction "I0_8") (pintype "input"))
      (node (ref "A15") (pin "5") (pinfunction "Q_5") (pintype "output"))
      (node (ref "A20") (pin "6") (pinfunction "I1_6") (pintype "input"))
      (node (ref "A20") (pin "8") (pinfunction "I0_8") (pintype "input"))
      (node (ref "A29") (pin "11") (pinfunction "I2_11") (pintype "input"))
      (node (ref "A29") (pin "4") (pinfunction "I1_4") (pintype "input"))
      (node (ref "A40") (pin "2") (pinfunction "I1_2") (pintype "input"))
      (node (ref "A41") (pin "12") (pinfunction "I0_12") (pintype "input"))
      (node (ref "A42") (pin "6") (pinfunction "I1_6") (pintype "input"))
    )
    (net (code "46") (name "/END_DMA") (class "Default")
      (node (ref "A30") (pin "11") (pinfunction "CLK_11") (pintype "input"))
      (node (ref "A30") (pin "3") (pinfunction "CLK_3") (pintype "input"))
      (node (ref "A41") (pin "8") (pinfunction "O_8") (pintype "output"))
    )
    (net (code "47") (name "/INITIALIZE") (class "Default")
      (node (ref "A9") (pin "7") (pinfunction "I1_7") (pintype "input"))
      (node (ref "U$2") (pin "CR1") (pinfunction "1_CR1") (pintype "bidirectional"))
    )
    (net (code "48") (name "/INTSTROBE") (class "Default")
      (node (ref "A26") (pin "3") (pinfunction "CLK_3") (pintype "input"))
      (node (ref "A7") (pin "14") (pinfunction "O_14") (pintype "output"))
    )
    (net (code "49") (name "/INT_STROBE") (class "Default")
      (node (ref "A7") (pin "9") (pinfunction "I0_9") (pintype "input"))
      (node (ref "U$2") (pin "BD2") (pinfunction "1_BD2") (pintype "bidirectional"))
    )
    (net (code "50") (name "/IOT76X") (class "Default")
      (node (ref "A54") (pin "6") (pinfunction "O_6") (pintype "output"))
      (node (ref "A56") (pin "13") (pinfunction "I2_13") (pintype "input"))
    )
    (net (code "51") (name "/IOT77X") (class "Default")
      (node (ref "A54") (pin "3") (pinfunction "O_3") (pintype "output"))
      (node (ref "A56") (pin "5") (pinfunction "I2_5") (pintype "input"))
    )
    (net (code "52") (name "/IOTP4") (class "Default")
      (node (ref "A52") (pin "12") (pinfunction "O_12") (pintype "open_collector"))
      (node (ref "CDJ1") (pin "15") (pinfunction "S_15") (pintype "passive"))
    )
    (net (code "53") (name "/IO_PAUSE") (class "Default")
      (node (ref "A18") (pin "2") (pinfunction "I1_2") (pintype "input"))
      (node (ref "A18") (pin "3") (pinfunction "I2_3") (pintype "input"))
      (node (ref "A18") (pin "4") (pinfunction "I3_4") (pintype "input"))
      (node (ref "A42") (pin "5") (pinfunction "I0_5") (pintype "input"))
      (node (ref "A9") (pin "13") (pinfunction "O_13") (pintype "output"))
    )
    (net (code "54") (name "/LATCH_MD") (class "Default")
      (node (ref "A13") (pin "10") (pinfunction "CLK_10") (pintype "input"))
      (node (ref "A17") (pin "10") (pinfunction "CLK_10") (pintype "input"))
      (node (ref "A22") (pin "10") (pinfunction "CLK_10") (pintype "input"))
      (node (ref "A29") (pin "8") (pinfunction "O_8") (pintype "output"))
    )
    (net (code "55") (name "/MALC") (class "Default")
      (node (ref "A26") (pin "9") (pinfunction "Q_9") (pintype "output"))
      (node (ref "A34") (pin "3") (pinfunction "I1_3") (pintype "input"))
      (node (ref "A4") (pin "5") (pinfunction "I0_5") (pintype "input"))
      (node (ref "A4") (pin "6") (pinfunction "I1_6") (pintype "input"))
    )
    (net (code "56") (name "/MD00") (class "Default")
      (node (ref "A13") (pin "4") (pinfunction "A_4") (pintype "input"))
      (node (ref "A2") (pin "14") (pinfunction "O_14") (pintype "output"))
      (node (ref "A23") (pin "3") (pinfunction "1B_3") (pintype "input"))
    )
    (net (code "57") (name "/MD01") (class "Default")
      (node (ref "A13") (pin "5") (pinfunction "B_5") (pintype "input"))
      (node (ref "A2") (pin "13") (pinfunction "O_13") (pintype "output"))
      (node (ref "A23") (pin "6") (pinfunction "2B_6") (pintype "input"))
    )
    (net (code "58") (name "/MD02") (class "Default")
      (node (ref "A13") (pin "6") (pinfunction "C_6") (pintype "input"))
      (node (ref "A2") (pin "3") (pinfunction "O_3") (pintype "output"))
      (node (ref "A23") (pin "10") (pinfunction "3B_10") (pintype "input"))
    )
    (net (code "59") (name "/MD03") (class "Default")
      (node (ref "A13") (pin "7") (pinfunction "D_7") (pintype "input"))
      (node (ref "A18") (pin "1") (pinfunction "I0_1") (pintype "input"))
      (node (ref "A2") (pin "2") (pinfunction "O_2") (pintype "output"))
      (node (ref "A23") (pin "13") (pinfunction "4B_13") (pintype "input"))
    )
    (net (code "60") (name "/MD04") (class "Default")
      (node (ref "A17") (pin "4") (pinfunction "A_4") (pintype "input"))
      (node (ref "A18") (pin "12") (pinfunction "I7_12") (pintype "input"))
      (node (ref "A27") (pin "3") (pinfunction "1B_3") (pintype "input"))
      (node (ref "A6") (pin "14") (pinfunction "O_14") (pintype "output"))
    )
    (net (code "61") (name "/MD05") (class "Default")
      (node (ref "A17") (pin "5") (pinfunction "B_5") (pintype "input"))
      (node (ref "A18") (pin "11") (pinfunction "I6_11") (pintype "input"))
      (node (ref "A27") (pin "6") (pinfunction "2B_6") (pintype "input"))
      (node (ref "A6") (pin "13") (pinfunction "O_13") (pintype "output"))
    )
    (net (code "62") (name "/MD06") (class "Default")
      (node (ref "A17") (pin "6") (pinfunction "C_6") (pintype "input"))
      (node (ref "A18") (pin "10") (pinfunction "P$2_10") (pintype "bidirectional"))
      (node (ref "A18") (pin "5") (pinfunction "I4_5") (pintype "input"))
      (node (ref "A27") (pin "10") (pinfunction "3B_10") (pintype "input"))
      (node (ref "A6") (pin "3") (pinfunction "O_3") (pintype "output"))
    )
    (net (code "63") (name "/MD07") (class "Default")
      (node (ref "A17") (pin "7") (pinfunction "D_7") (pintype "input"))
      (node (ref "A18") (pin "6") (pinfunction "I5_6") (pintype "input"))
      (node (ref "A18") (pin "9") (pinfunction "P$2_9") (pintype "bidirectional"))
      (node (ref "A27") (pin "13") (pinfunction "4B_13") (pintype "input"))
      (node (ref "A6") (pin "2") (pinfunction "O_2") (pintype "output"))
    )
    (net (code "64") (name "/MD08") (class "Default")
      (node (ref "A11") (pin "14") (pinfunction "O_14") (pintype "output"))
      (node (ref "A22") (pin "4") (pinfunction "A_4") (pintype "input"))
      (node (ref "A32") (pin "3") (pinfunction "1B_3") (pintype "input"))
      (node (ref "A48") (pin "11") (pinfunction "I_11") (pintype "input"))
      (node (ref "A54") (pin "1") (pinfunction "I0_1") (pintype "input"))
      (node (ref "A57") (pin "5") (pinfunction "I_5") (pintype "input"))
    )
    (net (code "65") (name "/MD08L") (class "Default")
      (node (ref "A48") (pin "10") (pinfunction "O_10") (pintype "output"))
      (node (ref "A54") (pin "4") (pinfunction "I0_4") (pintype "input"))
    )
    (net (code "66") (name "/MD09") (class "Default")
      (node (ref "A11") (pin "13") (pinfunction "O_13") (pintype "output"))
      (node (ref "A22") (pin "5") (pinfunction "B_5") (pintype "input"))
      (node (ref "A32") (pin "6") (pinfunction "2B_6") (pintype "input"))
      (node (ref "A48") (pin "13") (pinfunction "I_13") (pintype "input"))
      (node (ref "A55") (pin "1") (pinfunction "I0_1") (pintype "input"))
      (node (ref "A57") (pin "3") (pinfunction "I_3") (pintype "input"))
    )
    (net (code "67") (name "/MD09L") (class "Default")
      (node (ref "A48") (pin "12") (pinfunction "O_12") (pintype "output"))
      (node (ref "A56") (pin "1") (pinfunction "I0_1") (pintype "input"))
      (node (ref "A56") (pin "4") (pinfunction "I1_4") (pintype "input"))
    )
    (net (code "68") (name "/MD10") (class "Default")
      (node (ref "A11") (pin "3") (pinfunction "O_3") (pintype "output"))
      (node (ref "A22") (pin "6") (pinfunction "C_6") (pintype "input"))
      (node (ref "A32") (pin "10") (pinfunction "3B_10") (pintype "input"))
      (node (ref "A56") (pin "3") (pinfunction "I0_3") (pintype "input"))
      (node (ref "A57") (pin "1") (pinfunction "I_1") (pintype "input"))
    )
    (net (code "69") (name "/MD11") (class "Default")
      (node (ref "A11") (pin "2") (pinfunction "O_2") (pintype "output"))
      (node (ref "A22") (pin "7") (pinfunction "D_7") (pintype "input"))
      (node (ref "A32") (pin "13") (pinfunction "4B_13") (pintype "input"))
      (node (ref "A56") (pin "2") (pinfunction "I1_2") (pintype "input"))
      (node (ref "A57") (pin "13") (pinfunction "I_13") (pintype "input"))
    )
    (net (code "70") (name "/MD{slash}~{DATA}") (class "Default")
      (node (ref "A23") (pin "1") (pinfunction "~{A}/B_1") (pintype "input"))
      (node (ref "A27") (pin "1") (pinfunction "~{A}/B_1") (pintype "input"))
      (node (ref "A32") (pin "1") (pinfunction "~{A}/B_1") (pintype "input"))
      (node (ref "A37") (pin "11") (pinfunction "O_11") (pintype "output"))
      (node (ref "A42") (pin "11") (pinfunction "I0_11") (pintype "input"))
    )
    (net (code "71") (name "/MUX00") (class "Default")
      (node (ref "A23") (pin "4") (pinfunction "1Y_4") (pintype "output"))
      (node (ref "A52") (pin "1") (pinfunction "I_1") (pintype "input"))
    )
    (net (code "72") (name "/MUX01") (class "Default")
      (node (ref "A23") (pin "7") (pinfunction "2Y_7") (pintype "output"))
      (node (ref "A52") (pin "3") (pinfunction "I_3") (pintype "input"))
    )
    (net (code "73") (name "/MUX02") (class "Default")
      (node (ref "A23") (pin "9") (pinfunction "3Y_9") (pintype "output"))
      (node (ref "A52") (pin "9") (pinfunction "I_9") (pintype "input"))
    )
    (net (code "74") (name "/MUX03") (class "Default")
      (node (ref "A23") (pin "12") (pinfunction "4Y_12") (pintype "output"))
      (node (ref "A52") (pin "5") (pinfunction "I_5") (pintype "input"))
    )
    (net (code "75") (name "/MUX04") (class "Default")
      (node (ref "A27") (pin "4") (pinfunction "1Y_4") (pintype "output"))
      (node (ref "A47") (pin "1") (pinfunction "I_1") (pintype "input"))
    )
    (net (code "76") (name "/MUX05") (class "Default")
      (node (ref "A27") (pin "7") (pinfunction "2Y_7") (pintype "output"))
      (node (ref "A47") (pin "3") (pinfunction "I_3") (pintype "input"))
    )
    (net (code "77") (name "/MUX06") (class "Default")
      (node (ref "A27") (pin "9") (pinfunction "3Y_9") (pintype "output"))
      (node (ref "A47") (pin "9") (pinfunction "I_9") (pintype "input"))
    )
    (net (code "78") (name "/MUX07") (class "Default")
      (node (ref "A27") (pin "12") (pinfunction "4Y_12") (pintype "output"))
      (node (ref "A47") (pin "5") (pinfunction "I_5") (pintype "input"))
    )
    (net (code "79") (name "/MUX08") (class "Default")
      (node (ref "A32") (pin "4") (pinfunction "1Y_4") (pintype "output"))
      (node (ref "A51") (pin "1") (pinfunction "I_1") (pintype "input"))
    )
    (net (code "80") (name "/MUX09") (class "Default")
      (node (ref "A32") (pin "7") (pinfunction "2Y_7") (pintype "output"))
      (node (ref "A51") (pin "3") (pinfunction "I_3") (pintype "input"))
    )
    (net (code "81") (name "/MUX10") (class "Default")
      (node (ref "A32") (pin "9") (pinfunction "3Y_9") (pintype "output"))
      (node (ref "A51") (pin "9") (pinfunction "I_9") (pintype "input"))
    )
    (net (code "82") (name "/MUX11") (class "Default")
      (node (ref "A32") (pin "12") (pinfunction "4Y_12") (pintype "output"))
      (node (ref "A51") (pin "5") (pinfunction "I_5") (pintype "input"))
    )
    (net (code "83") (name "/MY_DMA") (class "Default")
      (node (ref "A15") (pin "12") (pinfunction "D_12") (pintype "input"))
      (node (ref "A15") (pin "2") (pinfunction "D_2") (pintype "input"))
      (node (ref "A37") (pin "8") (pinfunction "O_8") (pintype "output"))
      (node (ref "A41") (pin "10") (pinfunction "I1_10") (pintype "input"))
      (node (ref "A41") (pin "5") (pinfunction "I1_5") (pintype "input"))
    )
    (net (code "84") (name "/MY_IOT") (class "Default")
      (node (ref "A41") (pin "1") (pinfunction "I0_1") (pintype "input"))
      (node (ref "A43") (pin "8") (pinfunction "O_8") (pintype "output"))
      (node (ref "A51") (pin "13") (pinfunction "I_13") (pintype "input"))
      (node (ref "A54") (pin "2") (pinfunction "I1_2") (pintype "input"))
      (node (ref "A54") (pin "5") (pinfunction "I1_5") (pintype "input"))
      (node (ref "A55") (pin "2") (pinfunction "I1_2") (pintype "input"))
      (node (ref "A8") (pin "5") (pinfunction "I0_5") (pintype "input"))
      (node (ref "A8") (pin "6") (pinfunction "I1_6") (pintype "input"))
    )
    (net (code "85") (name "/N$187") (class "Default")
      (node (ref "A19") (pin "8") (pinfunction "I0_8") (pintype "input"))
      (node (ref "A19") (pin "9") (pinfunction "I1_9") (pintype "input"))
      (node (ref "R4") (pin "1") (pinfunction "1_1") (pintype "passive"))
    )
    (net (code "86") (name "/NODATAIOT") (class "Default")
      (node (ref "A41") (pin "3") (pinfunction "O_3") (pintype "output"))
      (node (ref "A42") (pin "12") (pinfunction "I1_12") (pintype "input"))
      (node (ref "A42") (pin "2") (pinfunction "I0_2") (pintype "input"))
    )
    (net (code "87") (name "/OVERFLOW") (class "Default")
      (node (ref "A40") (pin "1") (pinfunction "I0_1") (pintype "input"))
      (node (ref "A9") (pin "14") (pinfunction "O_14") (pintype "output"))
    )
    (net (code "88") (name "/RUN") (class "Default")
      (node (ref "A49") (pin "1") (pinfunction "I0_1") (pintype "input"))
      (node (ref "A49") (pin "2") (pinfunction "I1_2") (pintype "input"))
      (node (ref "A50") (pin "14") (pinfunction "O_14") (pintype "output"))
    )
    (net (code "89") (name "/TP1") (class "Default")
      (node (ref "A7") (pin "11") (pinfunction "I0_11") (pintype "input"))
      (node (ref "U$2") (pin "CD2") (pinfunction "1_CD2") (pintype "bidirectional"))
    )
    (net (code "90") (name "/TP3") (class "Default")
      (node (ref "A7") (pin "7") (pinfunction "I1_7") (pintype "input"))
      (node (ref "U$2") (pin "CH2") (pinfunction "1_CH2") (pintype "bidirectional"))
    )
    (net (code "91") (name "/TP4") (class "Default")
      (node (ref "A29") (pin "13") (pinfunction "I2_13") (pintype "input"))
      (node (ref "U$2") (pin "CJ2") (pinfunction "1_CJ2") (pintype "bidirectional"))
    )
    (net (code "92") (name "/TS2") (class "Default")
      (node (ref "A40") (pin "11") (pinfunction "I2_11") (pintype "input"))
      (node (ref "A41") (pin "13") (pinfunction "I1_13") (pintype "input"))
      (node (ref "A50") (pin "13") (pinfunction "O_13") (pintype "output"))
    )
    (net (code "93") (name "/TS4") (class "Default")
      (node (ref "A4") (pin "11") (pinfunction "I0_11") (pintype "input"))
      (node (ref "A9") (pin "3") (pinfunction "O_3") (pintype "output"))
    )
    (net (code "94") (name "/WANT_DATA") (class "Default")
      (node (ref "A24") (pin "10") (pinfunction "I1_10") (pintype "input"))
      (node (ref "A24") (pin "12") (pinfunction "I1_12") (pintype "input"))
      (node (ref "A24") (pin "4") (pinfunction "I0_4") (pintype "input"))
      (node (ref "A24") (pin "6") (pinfunction "I0_6") (pintype "input"))
      (node (ref "A28") (pin "10") (pinfunction "I1_10") (pintype "input"))
      (node (ref "A28") (pin "12") (pinfunction "I1_12") (pintype "input"))
      (node (ref "A28") (pin "4") (pinfunction "I0_4") (pintype "input"))
      (node (ref "A28") (pin "6") (pinfunction "I0_6") (pintype "input"))
      (node (ref "A33") (pin "10") (pinfunction "I1_10") (pintype "input"))
      (node (ref "A33") (pin "12") (pinfunction "I1_12") (pintype "input"))
      (node (ref "A33") (pin "4") (pinfunction "I0_4") (pintype "input"))
      (node (ref "A33") (pin "6") (pinfunction "I0_6") (pintype "input"))
      (node (ref "A42") (pin "1") (pinfunction "O_1") (pintype "output"))
      (node (ref "R8") (pin "1") (pinfunction "1_1") (pintype "passive"))
    )
    (net (code "95") (name "/WANT_DMA") (class "Default")
      (node (ref "A20") (pin "11") (pinfunction "I0_11") (pintype "input"))
      (node (ref "A20") (pin "12") (pinfunction "I1_12") (pintype "input"))
      (node (ref "A26") (pin "5") (pinfunction "Q_5") (pintype "output"))
      (node (ref "A37") (pin "10") (pinfunction "I1_10") (pintype "input"))
      (node (ref "A4") (pin "12") (pinfunction "I1_12") (pintype "input"))
      (node (ref "A4") (pin "8") (pinfunction "I0_8") (pintype "input"))
      (node (ref "A4") (pin "9") (pinfunction "I1_9") (pintype "input"))
      (node (ref "A42") (pin "3") (pinfunction "I1_3") (pintype "input"))
    )
    (net (code "96") (name "/WANT_MD") (class "Default")
      (node (ref "A11") (pin "10") (pinfunction "I1_10") (pintype "input"))
      (node (ref "A11") (pin "12") (pinfunction "I1_12") (pintype "input"))
      (node (ref "A11") (pin "4") (pinfunction "I0_4") (pintype "input"))
      (node (ref "A11") (pin "6") (pinfunction "I0_6") (pintype "input"))
      (node (ref "A2") (pin "10") (pinfunction "I1_10") (pintype "input"))
      (node (ref "A2") (pin "12") (pinfunction "I1_12") (pintype "input"))
      (node (ref "A2") (pin "4") (pinfunction "I0_4") (pintype "input"))
      (node (ref "A2") (pin "6") (pinfunction "I0_6") (pintype "input"))
      (node (ref "A42") (pin "4") (pinfunction "O_4") (pintype "output"))
      (node (ref "A6") (pin "10") (pinfunction "I1_10") (pintype "input"))
      (node (ref "A6") (pin "12") (pinfunction "I1_12") (pintype "input"))
      (node (ref "A6") (pin "4") (pinfunction "I0_4") (pintype "input"))
      (node (ref "A6") (pin "6") (pinfunction "I0_6") (pintype "input"))
      (node (ref "R1") (pin "2") (pinfunction "2_2") (pintype "passive"))
    )
    (net (code "97") (name "/WC") (class "Default")
      (node (ref "A29") (pin "5") (pinfunction "I2_5") (pintype "input"))
      (node (ref "A30") (pin "2") (pinfunction "D_2") (pintype "input"))
      (node (ref "A30") (pin "9") (pinfunction "Q_9") (pintype "output"))
      (node (ref "A42") (pin "8") (pinfunction "I0_8") (pintype "input"))
    )
    (net (code "98") (name "/WC{slash}~{ADDR}") (class "Default")
      (node (ref "A20") (pin "3") (pinfunction "I1_3") (pintype "input"))
      (node (ref "A31") (pin "8") (pinfunction "~{Q}_8") (pintype "output"))
      (node (ref "A38") (pin "11") (pinfunction "I_11") (pintype "input"))
      (node (ref "A4") (pin "3") (pinfunction "I1_3") (pintype "input"))
    )
    (net (code "99") (name "/XDONE") (class "Default")
      (node (ref "A19") (pin "2") (pinfunction "I0_2") (pintype "input"))
      (node (ref "A19") (pin "5") (pinfunction "I0_5") (pintype "input"))
      (node (ref "A20") (pin "5") (pinfunction "I0_5") (pintype "input"))
      (node (ref "A46") (pin "8") (pinfunction "O_8") (pintype "output"))
      (node (ref "A49") (pin "4") (pinfunction "I0_4") (pintype "input"))
      (node (ref "A55") (pin "13") (pinfunction "I1_13") (pintype "input"))
      (node (ref "A55") (pin "9") (pinfunction "I0_9") (pintype "input"))
      (node (ref "A8") (pin "11") (pinfunction "I0_11") (pintype "input"))
      (node (ref "A8") (pin "2") (pinfunction "I0_2") (pintype "input"))
    )
    (net (code "100") (name "/XEMA0") (class "Default")
      (node (ref "A34") (pin "12") (pinfunction "I1_12") (pintype "input"))
      (node (ref "A45") (pin "10") (pinfunction "O_10") (pintype "output"))
    )
    (net (code "101") (name "/XEMA1") (class "Default")
      (node (ref "A34") (pin "9") (pinfunction "I1_9") (pintype "input"))
      (node (ref "A45") (pin "12") (pinfunction "O_12") (pintype "output"))
    )
    (net (code "102") (name "/XEMA2") (class "Default")
      (node (ref "A34") (pin "5") (pinfunction "I0_5") (pintype "input"))
      (node (ref "A52") (pin "10") (pinfunction "O_10") (pintype "open_collector"))
      (node (ref "R9") (pin "1") (pinfunction "1_1") (pintype "passive"))
    )
    (net (code "103") (name "/~{(676[13]+677[23]})") (class "Default")
      (node (ref "A41") (pin "2") (pinfunction "I1_2") (pintype "input"))
      (node (ref "A48") (pin "6") (pinfunction "O_6") (pintype "output"))
      (node (ref "A49") (pin "13") (pinfunction "I1_13") (pintype "input"))
    )
    (net (code "104") (name "/~{BINITIALIZE}") (class "Default")
      (node (ref "A48") (pin "3") (pinfunction "I_3") (pintype "input"))
      (node (ref "A49") (pin "5") (pinfunction "I1_5") (pintype "input"))
      (node (ref "A55") (pin "6") (pinfunction "O_6") (pintype "output"))
    )
    (net (code "105") (name "/~{BREAK_CYCLE}") (class "Default")
      (node (ref "A8") (pin "10") (pinfunction "O_10") (pintype "open_collector"))
      (node (ref "U$2") (pin "BL2") (pinfunction "1_BL2") (pintype "bidirectional"))
    )
    (net (code "106") (name "/~{BRK_DATA_CONT}") (class "Default")
      (node (ref "A4") (pin "1") (pinfunction "O_1") (pintype "open_collector"))
      (node (ref "U$2") (pin "BK2") (pinfunction "1_BK2") (pintype "bidirectional"))
    )
    (net (code "107") (name "/~{BRK_IN_PROG}") (class "Default")
      (node (ref "A4") (pin "10") (pinfunction "O_10") (pintype "open_collector"))
      (node (ref "U$2") (pin "BE2") (pinfunction "1_BE2") (pintype "bidirectional"))
    )
    (net (code "108") (name "/~{C0}") (class "Default")
      (node (ref "A8") (pin "13") (pinfunction "O_13") (pintype "open_collector"))
      (node (ref "U$2") (pin "CE1") (pinfunction "1_CE1") (pintype "bidirectional"))
    )
    (net (code "109") (name "/~{C1}") (class "Default")
      (node (ref "A8") (pin "1") (pinfunction "O_1") (pintype "open_collector"))
      (node (ref "U$2") (pin "CH1") (pinfunction "1_CH1") (pintype "bidirectional"))
    )
    (net (code "110") (name "/~{CA}") (class "Default")
      (node (ref "A30") (pin "6") (pinfunction "~{Q}_6") (pintype "output"))
      (node (ref "A40") (pin "13") (pinfunction "I2_13") (pintype "input"))
      (node (ref "A40") (pin "4") (pinfunction "I1_4") (pintype "input"))
    )
    (net (code "111") (name "/~{CDJ1P25}") (class "Default")
      (node (ref "A38") (pin "9") (pinfunction "I_9") (pintype "input"))
      (node (ref "A40") (pin "9") (pinfunction "I0_9") (pintype "input"))
      (node (ref "A46") (pin "12") (pinfunction "O_12") (pintype "output"))
    )
    (net (code "112") (name "/~{CPMA_DISABLE}") (class "Default")
      (node (ref "A20") (pin "13") (pinfunction "O_13") (pintype "open_collector"))
      (node (ref "U$2") (pin "CU1") (pinfunction "1_CU1") (pintype "bidirectional"))
    )
    (net (code "113") (name "/~{DATA0}") (class "Default")
      (node (ref "A24") (pin "9") (pinfunction "I0_9") (pintype "input"))
      (node (ref "A3") (pin "1") (pinfunction "1_1") (pintype "passive"))
      (node (ref "A35") (pin "10") (pinfunction "O_10") (pintype "open_collector"))
      (node (ref "U$2") (pin "AR1") (pinfunction "1_AR1") (pintype "bidirectional"))
    )
    (net (code "114") (name "/~{DATA1}") (class "Default")
      (node (ref "A24") (pin "11") (pinfunction "I0_11") (pintype "input"))
      (node (ref "A3") (pin "2") (pinfunction "2_2") (pintype "passive"))
      (node (ref "A35") (pin "13") (pinfunction "O_13") (pintype "open_collector"))
      (node (ref "U$2") (pin "AS1") (pinfunction "1_AS1") (pintype "bidirectional"))
    )
    (net (code "115") (name "/~{DATA2}") (class "Default")
      (node (ref "A24") (pin "5") (pinfunction "I1_5") (pintype "input"))
      (node (ref "A3") (pin "3") (pinfunction "3_3") (pintype "passive"))
      (node (ref "A35") (pin "1") (pinfunction "O_1") (pintype "open_collector"))
      (node (ref "U$2") (pin "AU1") (pinfunction "1_AU1") (pintype "bidirectional"))
    )
    (net (code "116") (name "/~{DATA3}") (class "Default")
      (node (ref "A24") (pin "7") (pinfunction "I1_7") (pintype "input"))
      (node (ref "A3") (pin "4") (pinfunction "4_4") (pintype "passive"))
      (node (ref "A35") (pin "4") (pinfunction "O_4") (pintype "open_collector"))
      (node (ref "U$2") (pin "AV1") (pinfunction "1_AV1") (pintype "bidirectional"))
    )
    (net (code "117") (name "/~{DATA4}") (class "Default")
      (node (ref "A28") (pin "9") (pinfunction "I0_9") (pintype "input"))
      (node (ref "A3") (pin "5") (pinfunction "5_5") (pintype "passive"))
      (node (ref "A39") (pin "10") (pinfunction "O_10") (pintype "open_collector"))
      (node (ref "U$2") (pin "BR1") (pinfunction "1_BR1") (pintype "bidirectional"))
    )
    (net (code "118") (name "/~{DATA5}") (class "Default")
      (node (ref "A28") (pin "11") (pinfunction "I0_11") (pintype "input"))
      (node (ref "A39") (pin "13") (pinfunction "O_13") (pintype "open_collector"))
      (node (ref "U$2") (pin "BS1") (pinfunction "1_BS1") (pintype "bidirectional"))
    )
    (net (code "119") (name "/~{DATA6}") (class "Default")
      (node (ref "A28") (pin "5") (pinfunction "I1_5") (pintype "input"))
      (node (ref "A39") (pin "1") (pinfunction "O_1") (pintype "open_collector"))
      (node (ref "U$2") (pin "BU1") (pinfunction "1_BU1") (pintype "bidirectional"))
    )
    (net (code "120") (name "/~{DATA7}") (class "Default")
      (node (ref "A28") (pin "7") (pinfunction "I1_7") (pintype "input"))
      (node (ref "A39") (pin "4") (pinfunction "O_4") (pintype "open_collector"))
      (node (ref "U$2") (pin "BV1") (pinfunction "1_BV1") (pintype "bidirectional"))
    )
    (net (code "121") (name "/~{DATA8}") (class "Default")
      (node (ref "A33") (pin "9") (pinfunction "I0_9") (pintype "input"))
      (node (ref "A44") (pin "10") (pinfunction "O_10") (pintype "open_collector"))
      (node (ref "U$2") (pin "DR1") (pinfunction "1_DR1") (pintype "bidirectional"))
    )
    (net (code "122") (name "/~{DATA9}") (class "Default")
      (node (ref "A33") (pin "11") (pinfunction "I0_11") (pintype "input"))
      (node (ref "A44") (pin "13") (pinfunction "O_13") (pintype "open_collector"))
      (node (ref "U$2") (pin "DS1") (pinfunction "1_DS1") (pintype "bidirectional"))
    )
    (net (code "123") (name "/~{DATA10}") (class "Default")
      (node (ref "A33") (pin "5") (pinfunction "I1_5") (pintype "input"))
      (node (ref "A44") (pin "1") (pinfunction "O_1") (pintype "open_collector"))
      (node (ref "U$2") (pin "DU1") (pinfunction "1_DU1") (pintype "bidirectional"))
    )
    (net (code "124") (name "/~{DATA11}") (class "Default")
      (node (ref "A20") (pin "1") (pinfunction "O_1") (pintype "open_collector"))
      (node (ref "A33") (pin "7") (pinfunction "I1_7") (pintype "input"))
      (node (ref "A44") (pin "4") (pinfunction "O_4") (pintype "open_collector"))
      (node (ref "U$2") (pin "DV1") (pinfunction "1_DV1") (pintype "bidirectional"))
    )
    (net (code "125") (name "/~{EMA0}") (class "Default")
      (node (ref "A34") (pin "13") (pinfunction "O_13") (pintype "open_collector"))
      (node (ref "U$2") (pin "AD2") (pinfunction "1_AD2") (pintype "bidirectional"))
    )
    (net (code "126") (name "/~{EMA1}") (class "Default")
      (node (ref "A34") (pin "10") (pinfunction "O_10") (pintype "open_collector"))
      (node (ref "U$2") (pin "AE2") (pinfunction "1_AE2") (pintype "bidirectional"))
    )
    (net (code "127") (name "/~{EMA2}") (class "Default")
      (node (ref "A34") (pin "4") (pinfunction "O_4") (pintype "open_collector"))
      (node (ref "U$2") (pin "AH2") (pinfunction "1_AH2") (pintype "bidirectional"))
    )
    (net (code "128") (name "/~{INITIALIZE}") (class "Default")
      (node (ref "A55") (pin "4") (pinfunction "I0_4") (pintype "input"))
      (node (ref "A55") (pin "5") (pinfunction "I1_5") (pintype "input"))
      (node (ref "A9") (pin "2") (pinfunction "O_2") (pintype "output"))
    )
    (net (code "129") (name "/~{INTERNAL_IO}") (class "Default")
      (node (ref "A8") (pin "4") (pinfunction "O_4") (pintype "open_collector"))
      (node (ref "U$2") (pin "CL1") (pinfunction "1_CL1") (pintype "bidirectional"))
    )
    (net (code "130") (name "/~{INT_RQST}") (class "Default")
      (node (ref "A19") (pin "1") (pinfunction "O_1") (pintype "open_collector"))
      (node (ref "U$2") (pin "CP1") (pinfunction "1_CP1") (pintype "bidirectional"))
    )
    (net (code "131") (name "/~{IOD00}") (class "Default")
      (node (ref "A45") (pin "5") (pinfunction "I_5") (pintype "input"))
      (node (ref "A52") (pin "2") (pinfunction "O_2") (pintype "open_collector"))
      (node (ref "CDJ1") (pin "3") (pinfunction "S_3") (pintype "passive"))
    )
    (net (code "132") (name "/~{IOD01}") (class "Default")
      (node (ref "A45") (pin "3") (pinfunction "I_3") (pintype "input"))
      (node (ref "A52") (pin "4") (pinfunction "O_4") (pintype "open_collector"))
      (node (ref "CDJ1") (pin "5") (pinfunction "S_5") (pintype "passive"))
    )
    (net (code "133") (name "/~{IOD02}") (class "Default")
      (node (ref "A45") (pin "9") (pinfunction "I_9") (pintype "input"))
      (node (ref "A52") (pin "8") (pinfunction "O_8") (pintype "open_collector"))
      (node (ref "CDJ1") (pin "1") (pinfunction "S_1") (pintype "passive"))
    )
    (net (code "134") (name "/~{IOD03}") (class "Default")
      (node (ref "A45") (pin "1") (pinfunction "I_1") (pintype "input"))
      (node (ref "A52") (pin "6") (pinfunction "O_6") (pintype "open_collector"))
      (node (ref "CDJ1") (pin "7") (pinfunction "S_7") (pintype "passive"))
    )
    (net (code "135") (name "/~{IOD04}") (class "Default")
      (node (ref "A38") (pin "5") (pinfunction "I_5") (pintype "input"))
      (node (ref "A47") (pin "2") (pinfunction "O_2") (pintype "open_collector"))
      (node (ref "CCJ1") (pin "7") (pinfunction "S_7") (pintype "passive"))
    )
    (net (code "136") (name "/~{IOD05}") (class "Default")
      (node (ref "A38") (pin "3") (pinfunction "I_3") (pintype "input"))
      (node (ref "A47") (pin "4") (pinfunction "O_4") (pintype "open_collector"))
      (node (ref "CCJ1") (pin "5") (pinfunction "S_5") (pintype "passive"))
    )
    (net (code "137") (name "/~{IOD06}") (class "Default")
      (node (ref "A38") (pin "13") (pinfunction "I_13") (pintype "input"))
      (node (ref "A47") (pin "8") (pinfunction "O_8") (pintype "open_collector"))
      (node (ref "CCJ1") (pin "1") (pinfunction "S_1") (pintype "passive"))
    )
    (net (code "138") (name "/~{IOD07}") (class "Default")
      (node (ref "A38") (pin "1") (pinfunction "I_1") (pintype "input"))
      (node (ref "A47") (pin "6") (pinfunction "O_6") (pintype "open_collector"))
      (node (ref "CCJ1") (pin "3") (pinfunction "S_3") (pintype "passive"))
    )
    (net (code "139") (name "/~{IOD08}") (class "Default")
      (node (ref "A43") (pin "5") (pinfunction "I_5") (pintype "input"))
      (node (ref "A51") (pin "2") (pinfunction "O_2") (pintype "open_collector"))
      (node (ref "CDJ2") (pin "7") (pinfunction "S_7") (pintype "passive"))
    )
    (net (code "140") (name "/~{IOD09}") (class "Default")
      (node (ref "A43") (pin "3") (pinfunction "I_3") (pintype "input"))
      (node (ref "A51") (pin "4") (pinfunction "O_4") (pintype "open_collector"))
      (node (ref "CDJ2") (pin "5") (pinfunction "S_5") (pintype "passive"))
    )
    (net (code "141") (name "/~{IOD10}") (class "Default")
      (node (ref "A43") (pin "13") (pinfunction "I_13") (pintype "input"))
      (node (ref "A51") (pin "8") (pinfunction "O_8") (pintype "open_collector"))
      (node (ref "CDJ2") (pin "1") (pinfunction "S_1") (pintype "passive"))
    )
    (net (code "142") (name "/~{IOD11}") (class "Default")
      (node (ref "A43") (pin "1") (pinfunction "I_1") (pintype "input"))
      (node (ref "A51") (pin "6") (pinfunction "O_6") (pintype "open_collector"))
      (node (ref "CDJ2") (pin "3") (pinfunction "S_3") (pintype "passive"))
    )
    (net (code "143") (name "/~{IO_PAUSE}") (class "Default")
      (node (ref "A9") (pin "11") (pinfunction "I0_11") (pintype "input"))
      (node (ref "U$2") (pin "CD1") (pinfunction "1_CD1") (pintype "bidirectional"))
    )
    (net (code "144") (name "/~{LOAD_CONT}") (class "Default")
      (node (ref "A4") (pin "4") (pinfunction "O_4") (pintype "open_collector"))
      (node (ref "U$2") (pin "BH2") (pinfunction "1_BH2") (pintype "bidirectional"))
    )
    (net (code "145") (name "/~{MA00}") (class "Default")
      (node (ref "A1") (pin "10") (pinfunction "O_10") (pintype "open_collector"))
      (node (ref "U$2") (pin "AD1") (pinfunction "1_AD1") (pintype "bidirectional"))
    )
    (net (code "146") (name "/~{MA01}") (class "Default")
      (node (ref "A1") (pin "13") (pinfunction "O_13") (pintype "open_collector"))
      (node (ref "U$2") (pin "AE1") (pinfunction "1_AE1") (pintype "bidirectional"))
    )
    (net (code "147") (name "/~{MA02}") (class "Default")
      (node (ref "A1") (pin "4") (pinfunction "O_4") (pintype "open_collector"))
      (node (ref "U$2") (pin "AH1") (pinfunction "1_AH1") (pintype "bidirectional"))
    )
    (net (code "148") (name "/~{MA03}") (class "Default")
      (node (ref "A1") (pin "1") (pinfunction "O_1") (pintype "open_collector"))
      (node (ref "U$2") (pin "AJ1") (pinfunction "1_AJ1") (pintype "bidirectional"))
    )
    (net (code "149") (name "/~{MA04}") (class "Default")
      (node (ref "A5") (pin "10") (pinfunction "O_10") (pintype "open_collector"))
      (node (ref "U$2") (pin "BD1") (pinfunction "1_BD1") (pintype "bidirectional"))
    )
    (net (code "150") (name "/~{MA05}") (class "Default")
      (node (ref "A5") (pin "13") (pinfunction "O_13") (pintype "open_collector"))
      (node (ref "U$2") (pin "BE1") (pinfunction "1_BE1") (pintype "bidirectional"))
    )
    (net (code "151") (name "/~{MA06}") (class "Default")
      (node (ref "A5") (pin "4") (pinfunction "O_4") (pintype "open_collector"))
      (node (ref "U$2") (pin "BH1") (pinfunction "1_BH1") (pintype "bidirectional"))
    )
    (net (code "152") (name "/~{MA07}") (class "Default")
      (node (ref "A5") (pin "1") (pinfunction "O_1") (pintype "open_collector"))
      (node (ref "U$2") (pin "BJ1") (pinfunction "1_BJ1") (pintype "bidirectional"))
    )
    (net (code "153") (name "/~{MA08}") (class "Default")
      (node (ref "A10") (pin "10") (pinfunction "O_10") (pintype "open_collector"))
      (node (ref "U$2") (pin "DD1") (pinfunction "1_DD1") (pintype "bidirectional"))
    )
    (net (code "154") (name "/~{MA09}") (class "Default")
      (node (ref "A10") (pin "13") (pinfunction "O_13") (pintype "open_collector"))
      (node (ref "U$2") (pin "DE1") (pinfunction "1_DE1") (pintype "bidirectional"))
    )
    (net (code "155") (name "/~{MA10}") (class "Default")
      (node (ref "A10") (pin "4") (pinfunction "O_4") (pintype "open_collector"))
      (node (ref "U$2") (pin "DH1") (pinfunction "1_DH1") (pintype "bidirectional"))
    )
    (net (code "156") (name "/~{MA11}") (class "Default")
      (node (ref "A10") (pin "1") (pinfunction "O_1") (pintype "open_collector"))
      (node (ref "A20") (pin "10") (pinfunction "O_10") (pintype "open_collector"))
      (node (ref "U$2") (pin "DJ1") (pinfunction "1_DJ1") (pintype "bidirectional"))
    )
    (net (code "157") (name "/~{MD00}") (class "Default")
      (node (ref "A2") (pin "9") (pinfunction "I0_9") (pintype "input"))
      (node (ref "U$2") (pin "AK1") (pinfunction "1_AK1") (pintype "bidirectional"))
    )
    (net (code "158") (name "/~{MD01}") (class "Default")
      (node (ref "A2") (pin "11") (pinfunction "I0_11") (pintype "input"))
      (node (ref "U$2") (pin "AL1") (pinfunction "1_AL1") (pintype "bidirectional"))
    )
    (net (code "159") (name "/~{MD02}") (class "Default")
      (node (ref "A2") (pin "5") (pinfunction "I1_5") (pintype "input"))
      (node (ref "U$2") (pin "AM1") (pinfunction "1_AM1") (pintype "bidirectional"))
    )
    (net (code "160") (name "/~{MD03}") (class "Default")
      (node (ref "A2") (pin "7") (pinfunction "I1_7") (pintype "input"))
      (node (ref "U$2") (pin "AP1") (pinfunction "1_AP1") (pintype "bidirectional"))
    )
    (net (code "161") (name "/~{MD04}") (class "Default")
      (node (ref "A6") (pin "9") (pinfunction "I0_9") (pintype "input"))
      (node (ref "U$2") (pin "BK1") (pinfunction "1_BK1") (pintype "bidirectional"))
    )
    (net (code "162") (name "/~{MD05}") (class "Default")
      (node (ref "A6") (pin "11") (pinfunction "I0_11") (pintype "input"))
      (node (ref "U$2") (pin "BL1") (pinfunction "1_BL1") (pintype "bidirectional"))
    )
    (net (code "163") (name "/~{MD06}") (class "Default")
      (node (ref "A6") (pin "5") (pinfunction "I1_5") (pintype "input"))
      (node (ref "U$2") (pin "BM1") (pinfunction "1_BM1") (pintype "bidirectional"))
    )
    (net (code "164") (name "/~{MD07}") (class "Default")
      (node (ref "A6") (pin "7") (pinfunction "I1_7") (pintype "input"))
      (node (ref "U$2") (pin "BP1") (pinfunction "1_BP1") (pintype "bidirectional"))
    )
    (net (code "165") (name "/~{MD08}") (class "Default")
      (node (ref "A11") (pin "9") (pinfunction "I0_9") (pintype "input"))
      (node (ref "U$2") (pin "DK1") (pinfunction "1_DK1") (pintype "bidirectional"))
    )
    (net (code "166") (name "/~{MD09}") (class "Default")
      (node (ref "A11") (pin "11") (pinfunction "I0_11") (pintype "input"))
      (node (ref "U$2") (pin "DL1") (pinfunction "1_DL1") (pintype "bidirectional"))
    )
    (net (code "167") (name "/~{MD10}") (class "Default")
      (node (ref "A11") (pin "5") (pinfunction "I1_5") (pintype "input"))
      (node (ref "U$2") (pin "DM1") (pinfunction "1_DM1") (pintype "bidirectional"))
    )
    (net (code "168") (name "/~{MD11}") (class "Default")
      (node (ref "A11") (pin "7") (pinfunction "I1_7") (pintype "input"))
      (node (ref "U$2") (pin "DP1") (pinfunction "1_DP1") (pintype "bidirectional"))
    )
    (net (code "169") (name "/~{MD_DIR}") (class "Default")
      (node (ref "A34") (pin "1") (pinfunction "O_1") (pintype "open_collector"))
      (node (ref "U$2") (pin "AK2") (pinfunction "1_AK2") (pintype "bidirectional"))
    )
    (net (code "170") (name "/~{MS_DISABLE}") (class "Default")
      (node (ref "A20") (pin "4") (pinfunction "O_4") (pintype "open_collector"))
      (node (ref "U$2") (pin "CV1") (pinfunction "1_CV1") (pintype "bidirectional"))
    )
    (net (code "171") (name "/~{MY_IOT}") (class "Default")
      (node (ref "A18") (pin "8") (pinfunction "O_8") (pintype "output"))
      (node (ref "A31") (pin "4") (pinfunction "PRE_4") (pintype "input"))
      (node (ref "A43") (pin "9") (pinfunction "I_9") (pintype "input"))
    )
    (net (code "172") (name "/~{OVERFLOW}") (class "Default")
      (node (ref "A9") (pin "9") (pinfunction "I0_9") (pintype "input"))
      (node (ref "U$2") (pin "BJ2") (pinfunction "1_BJ2") (pintype "bidirectional"))
    )
    (net (code "173") (name "/~{RUN}") (class "Default")
      (node (ref "A50") (pin "9") (pinfunction "I0_9") (pintype "input"))
      (node (ref "U$2") (pin "BU2") (pinfunction "1_BU2") (pintype "bidirectional"))
    )
    (net (code "174") (name "/~{SKIP}") (class "Default")
      (node (ref "A19") (pin "4") (pinfunction "O_4") (pintype "open_collector"))
      (node (ref "U$2") (pin "CS1") (pinfunction "1_CS1") (pintype "bidirectional"))
    )
    (net (code "175") (name "/~{STOP_DMA}") (class "Default")
      (node (ref "A15") (pin "1") (pinfunction "CLR_1") (pintype "input"))
      (node (ref "A15") (pin "13") (pinfunction "CLR_13") (pintype "input"))
      (node (ref "A19") (pin "10") (pinfunction "O_10") (pintype "open_collector"))
      (node (ref "A19") (pin "13") (pinfunction "O_13") (pintype "open_collector"))
      (node (ref "A26") (pin "13") (pinfunction "CLR_13") (pintype "input"))
      (node (ref "A30") (pin "1") (pinfunction "CLR_1") (pintype "input"))
      (node (ref "A30") (pin "13") (pinfunction "CLR_13") (pintype "input"))
      (node (ref "A31") (pin "13") (pinfunction "CLR_13") (pintype "input"))
      (node (ref "A37") (pin "2") (pinfunction "I1_2") (pintype "input"))
      (node (ref "R5") (pin "1") (pinfunction "1_1") (pintype "passive"))
    )
    (net (code "176") (name "/~{TP4}") (class "Default")
      (node (ref "A15") (pin "11") (pinfunction "CLK_11") (pintype "input"))
      (node (ref "A15") (pin "3") (pinfunction "CLK_3") (pintype "input"))
      (node (ref "A29") (pin "12") (pinfunction "O_12") (pintype "output"))
      (node (ref "A31") (pin "11") (pinfunction "CLK_11") (pintype "input"))
      (node (ref "A41") (pin "9") (pinfunction "I0_9") (pintype "input"))
      (node (ref "A52") (pin "13") (pinfunction "I_13") (pintype "input"))
    )
    (net (code "177") (name "/~{TS2}") (class "Default")
      (node (ref "A50") (pin "11") (pinfunction "I0_11") (pintype "input"))
      (node (ref "U$2") (pin "CL2") (pinfunction "1_CL2") (pintype "bidirectional"))
    )
    (net (code "178") (name "/~{TS4}") (class "Default")
      (node (ref "A9") (pin "5") (pinfunction "I1_5") (pintype "input"))
      (node (ref "U$2") (pin "CP2") (pinfunction "1_CP2") (pintype "bidirectional"))
    )
    (net (code "179") (name "/~{WANT_MUX}") (class "Default")
      (node (ref "A23") (pin "15") (pinfunction "G_15") (pintype "input"))
      (node (ref "A27") (pin "15") (pinfunction "G_15") (pintype "input"))
      (node (ref "A32") (pin "15") (pinfunction "G_15") (pintype "input"))
      (node (ref "A42") (pin "13") (pinfunction "O_13") (pintype "output"))
    )
    (net (code "180") (name "/~{XEMA0}") (class "Default")
      (node (ref "A45") (pin "11") (pinfunction "I_11") (pintype "input"))
      (node (ref "A53") (pin "1") (pinfunction "TERM_1") (pintype "input"))
      (node (ref "CDJ1") (pin "9") (pinfunction "S_9") (pintype "passive"))
    )
    (net (code "181") (name "/~{XEMA1}") (class "Default")
      (node (ref "A45") (pin "13") (pinfunction "I_13") (pintype "input"))
      (node (ref "A53") (pin "2") (pinfunction "TERM_2") (pintype "input"))
      (node (ref "CDJ1") (pin "11") (pinfunction "S_11") (pintype "passive"))
    )
    (net (code "182") (name "/~{XEMA2}") (class "Default")
      (node (ref "A52") (pin "11") (pinfunction "I_11") (pintype "input"))
      (node (ref "A53") (pin "15") (pinfunction "TERM_15") (pintype "input"))
      (node (ref "CDJ1") (pin "13") (pinfunction "S_13") (pintype "passive"))
    )
    (net (code "183") (name "GND") (class "Default")
      (node (ref "A12") (pin "15") (pinfunction "G_15") (pintype "input"))
      (node (ref "A13") (pin "2") (pinfunction "J_2") (pintype "input"))
      (node (ref "A13") (pin "3") (pinfunction "K_3") (pintype "input"))
      (node (ref "A13") (pin "9") (pinfunction "S/~{L}_9") (pintype "input"))
      (node (ref "A16") (pin "15") (pinfunction "G_15") (pintype "input"))
      (node (ref "A16") (pin "5") (pinfunction "2A_5") (pintype "input"))
      (node (ref "A17") (pin "2") (pinfunction "J_2") (pintype "input"))
      (node (ref "A17") (pin "3") (pinfunction "K_3") (pintype "input"))
      (node (ref "A17") (pin "9") (pinfunction "S/~{L}_9") (pintype "input"))
      (node (ref "A21") (pin "15") (pinfunction "G_15") (pintype "input"))
      (node (ref "A21") (pin "2") (pinfunction "1A_2") (pintype "input"))
      (node (ref "A21") (pin "5") (pinfunction "2A_5") (pintype "input"))
      (node (ref "A22") (pin "2") (pinfunction "J_2") (pintype "input"))
      (node (ref "A22") (pin "3") (pinfunction "K_3") (pintype "input"))
      (node (ref "A22") (pin "9") (pinfunction "S/~{L}_9") (pintype "input"))
      (node (ref "A25") (pin "1") (pinfunction "1_1") (pintype "passive"))
      (node (ref "A25B") (pin "1") (pinfunction "1_1") (pintype "passive"))
      (node (ref "A25C") (pin "1") (pinfunction "1_1") (pintype "passive"))
      (node (ref "A25D") (pin "1") (pinfunction "1_1") (pintype "passive"))
      (node (ref "A50") (pin "10") (pinfunction "I1_10") (pintype "input"))
      (node (ref "A50") (pin "12") (pinfunction "I1_12") (pintype "input"))
      (node (ref "A7") (pin "10") (pinfunction "I1_10") (pintype "input"))
      (node (ref "A7") (pin "12") (pinfunction "I1_12") (pintype "input"))
      (node (ref "A7") (pin "4") (pinfunction "I0_4") (pintype "input"))
      (node (ref "A7") (pin "6") (pinfunction "I0_6") (pintype "input"))
      (node (ref "A9") (pin "10") (pinfunction "I1_10") (pintype "input"))
      (node (ref "A9") (pin "12") (pinfunction "I1_12") (pintype "input"))
      (node (ref "A9") (pin "4") (pinfunction "I0_4") (pintype "input"))
      (node (ref "A9") (pin "6") (pinfunction "I0_6") (pintype "input"))
      (node (ref "C1") (pin "2") (pinfunction "2_2") (pintype "passive"))
      (node (ref "C10") (pin "2") (pinfunction "2_2") (pintype "passive"))
      (node (ref "C11") (pin "2") (pinfunction "2_2") (pintype "passive"))
      (node (ref "C12") (pin "2") (pinfunction "2_2") (pintype "passive"))
      (node (ref "C13") (pin "2") (pinfunction "2_2") (pintype "passive"))
      (node (ref "C14") (pin "2") (pinfunction "2_2") (pintype "passive"))
      (node (ref "C15") (pin "2") (pinfunction "2_2") (pintype "passive"))
      (node (ref "C16") (pin "2") (pinfunction "2_2") (pintype "passive"))
      (node (ref "C17") (pin "2") (pinfunction "2_2") (pintype "passive"))
      (node (ref "C18") (pin "2") (pinfunction "2_2") (pintype "passive"))
      (node (ref "C19") (pin "2") (pinfunction "2_2") (pintype "passive"))
      (node (ref "C2") (pin "2") (pinfunction "2_2") (pintype "passive"))
      (node (ref "C20") (pin "2") (pinfunction "2_2") (pintype "passive"))
      (node (ref "C21") (pin "2") (pinfunction "2_2") (pintype "passive"))
      (node (ref "C22") (pin "2") (pinfunction "2_2") (pintype "passive"))
      (node (ref "C23") (pin "2") (pinfunction "2_2") (pintype "passive"))
      (node (ref "C24") (pin "2") (pinfunction "2_2") (pintype "passive"))
      (node (ref "C25") (pin "2") (pinfunction "2_2") (pintype "passive"))
      (node (ref "C26") (pin "2") (pinfunction "2_2") (pintype "passive"))
      (node (ref "C3") (pin "2") (pinfunction "2_2") (pintype "passive"))
      (node (ref "C4") (pin "2") (pinfunction "2_2") (pintype "passive"))
      (node (ref "C5") (pin "2") (pinfunction "2_2") (pintype "passive"))
      (node (ref "C6") (pin "2") (pinfunction "2_2") (pintype "passive"))
      (node (ref "C7") (pin "2") (pinfunction "2_2") (pintype "passive"))
      (node (ref "C8") (pin "2") (pinfunction "2_2") (pintype "passive"))
      (node (ref "C9") (pin "2") (pinfunction "2_2") (pintype "passive"))
      (node (ref "CCJ1") (pin "10") (pinfunction "S_10") (pintype "passive"))
      (node (ref "CCJ1") (pin "12") (pinfunction "S_12") (pintype "passive"))
      (node (ref "CCJ1") (pin "14") (pinfunction "S_14") (pintype "passive"))
      (node (ref "CCJ1") (pin "16") (pinfunction "S_16") (pintype "passive"))
      (node (ref "CCJ1") (pin "17") (pinfunction "S_17") (pintype "passive"))
      (node (ref "CCJ1") (pin "18") (pinfunction "S_18") (pintype "passive"))
      (node (ref "CCJ1") (pin "2") (pinfunction "S_2") (pintype "passive"))
      (node (ref "CCJ1") (pin "20") (pinfunction "S_20") (pintype "passive"))
      (node (ref "CCJ1") (pin "22") (pinfunction "S_22") (pintype "passive"))
      (node (ref "CCJ1") (pin "24") (pinfunction "S_24") (pintype "passive"))
      (node (ref "CCJ1") (pin "26") (pinfunction "S_26") (pintype "passive"))
      (node (ref "CCJ1") (pin "4") (pinfunction "S_4") (pintype "passive"))
      (node (ref "CCJ1") (pin "6") (pinfunction "S_6") (pintype "passive"))
      (node (ref "CCJ1") (pin "8") (pinfunction "S_8") (pintype "passive"))
      (node (ref "CDJ1") (pin "10") (pinfunction "S_10") (pintype "passive"))
      (node (ref "CDJ1") (pin "12") (pinfunction "S_12") (pintype "passive"))
      (node (ref "CDJ1") (pin "14") (pinfunction "S_14") (pintype "passive"))
      (node (ref "CDJ1") (pin "16") (pinfunction "S_16") (pintype "passive"))
      (node (ref "CDJ1") (pin "18") (pinfunction "S_18") (pintype "passive"))
      (node (ref "CDJ1") (pin "2") (pinfunction "S_2") (pintype "passive"))
      (node (ref "CDJ1") (pin "20") (pinfunction "S_20") (pintype "passive"))
      (node (ref "CDJ1") (pin "22") (pinfunction "S_22") (pintype "passive"))
      (node (ref "CDJ1") (pin "24") (pinfunction "S_24") (pintype "passive"))
      (node (ref "CDJ1") (pin "26") (pinfunction "S_26") (pintype "passive"))
      (node (ref "CDJ1") (pin "4") (pinfunction "S_4") (pintype "passive"))
      (node (ref "CDJ1") (pin "6") (pinfunction "S_6") (pintype "passive"))
      (node (ref "CDJ1") (pin "8") (pinfunction "S_8") (pintype "passive"))
      (node (ref "CDJ2") (pin "10") (pinfunction "S_10") (pintype "passive"))
      (node (ref "CDJ2") (pin "12") (pinfunction "S_12") (pintype "passive"))
      (node (ref "CDJ2") (pin "14") (pinfunction "S_14") (pintype "passive"))
      (node (ref "CDJ2") (pin "16") (pinfunction "S_16") (pintype "passive"))
      (node (ref "CDJ2") (pin "18") (pinfunction "S_18") (pintype "passive"))
      (node (ref "CDJ2") (pin "2") (pinfunction "S_2") (pintype "passive"))
      (node (ref "CDJ2") (pin "20") (pinfunction "S_20") (pintype "passive"))
      (node (ref "CDJ2") (pin "22") (pinfunction "S_22") (pintype "passive"))
      (node (ref "CDJ2") (pin "24") (pinfunction "S_24") (pintype "passive"))
      (node (ref "CDJ2") (pin "26") (pinfunction "S_26") (pintype "passive"))
      (node (ref "CDJ2") (pin "4") (pinfunction "S_4") (pintype "passive"))
      (node (ref "CDJ2") (pin "6") (pinfunction "S_6") (pintype "passive"))
      (node (ref "CDJ2") (pin "8") (pinfunction "S_8") (pintype "passive"))
      (node (ref "U$2") (pin "AC2") (pinfunction "1_AC2") (pintype "bidirectional"))
      (node (ref "U$2") (pin "AF1") (pinfunction "1_AF1") (pintype "bidirectional"))
      (node (ref "U$2") (pin "AF2") (pinfunction "1_AF2") (pintype "bidirectional"))
      (node (ref "U$2") (pin "AN1") (pinfunction "1_AN1") (pintype "bidirectional"))
      (node (ref "U$2") (pin "AN2") (pinfunction "1_AN2") (pintype "bidirectional"))
      (node (ref "U$2") (pin "AT1") (pinfunction "1_AT1") (pintype "bidirectional"))
      (node (ref "U$2") (pin "AT2") (pinfunction "1_AT2") (pintype "bidirectional"))
      (node (ref "U$2") (pin "BC1") (pinfunction "1_BC1") (pintype "bidirectional"))
      (node (ref "U$2") (pin "BC2") (pinfunction "1_BC2") (pintype "bidirectional"))
      (node (ref "U$2") (pin "BN1") (pinfunction "1_BN1") (pintype "bidirectional"))
      (node (ref "U$2") (pin "BN2") (pinfunction "1_BN2") (pintype "bidirectional"))
      (node (ref "U$2") (pin "BT1") (pinfunction "1_BT1") (pintype "bidirectional"))
      (node (ref "U$2") (pin "BT2") (pinfunction "1_BT2") (pintype "bidirectional"))
      (node (ref "U$2") (pin "CC1") (pinfunction "1_CC1") (pintype "bidirectional"))
      (node (ref "U$2") (pin "CC2") (pinfunction "1_CC2") (pintype "bidirectional"))
      (node (ref "U$2") (pin "CF1") (pinfunction "1_CF1") (pintype "bidirectional"))
      (node (ref "U$2") (pin "CF2") (pinfunction "1_CF2") (pintype "bidirectional"))
      (node (ref "U$2") (pin "CT1") (pinfunction "1_CT1") (pintype "bidirectional"))
      (node (ref "U$2") (pin "CT2") (pinfunction "1_CT2") (pintype "bidirectional"))
      (node (ref "U$2") (pin "DC1") (pinfunction "1_DC1") (pintype "bidirectional"))
      (node (ref "U$2") (pin "DC2") (pinfunction "1_DC2") (pintype "bidirectional"))
      (node (ref "U$2") (pin "DF1") (pinfunction "1_DF1") (pintype "bidirectional"))
      (node (ref "U$2") (pin "DF2") (pinfunction "1_DF2") (pintype "bidirectional"))
      (node (ref "U$2") (pin "DN1") (pinfunction "1_DN1") (pintype "bidirectional"))
      (node (ref "U$2") (pin "DN2") (pinfunction "1_DN2") (pintype "bidirectional"))
      (node (ref "U$2") (pin "DT1") (pinfunction "1_DT1") (pintype "bidirectional"))
      (node (ref "U$2") (pin "DT2") (pinfunction "1_DT2") (pintype "bidirectional"))
    )
    (net (code "184") (name "Net-(A4D-O)") (class "Default")
      (node (ref "A4") (pin "13") (pinfunction "O_13") (pintype "open_collector"))
      (node (ref "P") (pin "1") (pinfunction "P_1") (pintype "passive"))
    )
    (net (code "185") (name "Net-(A10A-I0)") (class "Default")
      (node (ref "A10") (pin "2") (pinfunction "I0_2") (pintype "input"))
      (node (ref "A21") (pin "7") (pinfunction "2Y_7") (pintype "output"))
    )
    (net (code "186") (name "Net-(A10B-I0)") (class "Default")
      (node (ref "A10") (pin "5") (pinfunction "I0_5") (pintype "input"))
      (node (ref "A21") (pin "4") (pinfunction "1Y_4") (pintype "output"))
    )
    (net (code "187") (name "Net-(A10C-I1)") (class "Default")
      (node (ref "A10") (pin "9") (pinfunction "I1_9") (pintype "input"))
      (node (ref "A21") (pin "9") (pinfunction "3Y_9") (pintype "output"))
    )
    (net (code "188") (name "Net-(A10D-I1)") (class "Default")
      (node (ref "A10") (pin "12") (pinfunction "I1_12") (pintype "input"))
      (node (ref "A21") (pin "12") (pinfunction "4Y_12") (pintype "output"))
    )
    (net (code "189") (name "Net-(A12A-1Y)") (class "Default")
      (node (ref "A1") (pin "5") (pinfunction "I0_5") (pintype "input"))
      (node (ref "A12") (pin "4") (pinfunction "1Y_4") (pintype "output"))
    )
    (net (code "190") (name "Net-(A12A-2Y)") (class "Default")
      (node (ref "A1") (pin "2") (pinfunction "I0_2") (pintype "input"))
      (node (ref "A12") (pin "7") (pinfunction "2Y_7") (pintype "output"))
    )
    (net (code "191") (name "Net-(A12A-3Y)") (class "Default")
      (node (ref "A1") (pin "9") (pinfunction "I1_9") (pintype "input"))
      (node (ref "A12") (pin "9") (pinfunction "3Y_9") (pintype "output"))
    )
    (net (code "192") (name "Net-(A12A-4Y)") (class "Default")
      (node (ref "A1") (pin "12") (pinfunction "I1_12") (pintype "input"))
      (node (ref "A12") (pin "12") (pinfunction "4Y_12") (pintype "output"))
    )
    (net (code "193") (name "Net-(A14B-I0)") (class "Default")
      (node (ref "A14") (pin "9") (pinfunction "I0_9") (pintype "input"))
      (node (ref "A25C") (pin "2") (pinfunction "2_2") (pintype "passive"))
    )
    (net (code "194") (name "Net-(A14B-I1)") (class "Default")
      (node (ref "A14") (pin "10") (pinfunction "I1_10") (pintype "input"))
      (node (ref "A25D") (pin "2") (pinfunction "2_2") (pintype "passive"))
    )
    (net (code "195") (name "Net-(A14B-I2)") (class "Default")
      (node (ref "A14") (pin "12") (pinfunction "I2_12") (pintype "input"))
      (node (ref "A25B") (pin "2") (pinfunction "2_2") (pintype "passive"))
    )
    (net (code "196") (name "Net-(A14B-I3)") (class "Default")
      (node (ref "A14") (pin "13") (pinfunction "I3_13") (pintype "input"))
      (node (ref "A25") (pin "2") (pinfunction "2_2") (pintype "passive"))
    )
    (net (code "197") (name "Net-(A14B-O)") (class "Default")
      (node (ref "A14") (pin "8") (pinfunction "O_8") (pintype "output"))
      (node (ref "A37") (pin "9") (pinfunction "I0_9") (pintype "input"))
    )
    (net (code "198") (name "Net-(A16A-1Y)") (class "Default")
      (node (ref "A16") (pin "4") (pinfunction "1Y_4") (pintype "output"))
      (node (ref "A5") (pin "5") (pinfunction "I0_5") (pintype "input"))
    )
    (net (code "199") (name "Net-(A16A-2Y)") (class "Default")
      (node (ref "A16") (pin "7") (pinfunction "2Y_7") (pintype "output"))
      (node (ref "A5") (pin "2") (pinfunction "I0_2") (pintype "input"))
    )
    (net (code "200") (name "Net-(A16A-3Y)") (class "Default")
      (node (ref "A16") (pin "9") (pinfunction "3Y_9") (pintype "output"))
      (node (ref "A5") (pin "9") (pinfunction "I1_9") (pintype "input"))
    )
    (net (code "201") (name "Net-(A16A-4Y)") (class "Default")
      (node (ref "A16") (pin "12") (pinfunction "4Y_12") (pintype "output"))
      (node (ref "A5") (pin "12") (pinfunction "I1_12") (pintype "input"))
    )
    (net (code "202") (name "Net-(A19A-I1)") (class "Default")
      (node (ref "A19") (pin "3") (pinfunction "I1_3") (pintype "input"))
      (node (ref "A46") (pin "4") (pinfunction "O_4") (pintype "output"))
    )
    (net (code "203") (name "Net-(A19B-I1)") (class "Default")
      (node (ref "A19") (pin "6") (pinfunction "I1_6") (pintype "input"))
      (node (ref "A46") (pin "6") (pinfunction "O_6") (pintype "output"))
    )
    (net (code "204") (name "Net-(A19D-I0)") (class "Default")
      (node (ref "A19") (pin "11") (pinfunction "I0_11") (pintype "input"))
      (node (ref "A19") (pin "12") (pinfunction "I1_12") (pintype "input"))
      (node (ref "A49") (pin "6") (pinfunction "O_6") (pintype "open_collector"))
    )
    (net (code "205") (name "Net-(A20A-I0)") (class "Default")
      (node (ref "A20") (pin "2") (pinfunction "I0_2") (pintype "input"))
      (node (ref "A41") (pin "11") (pinfunction "O_11") (pintype "output"))
    )
    (net (code "206") (name "Net-(A26A-CLR)") (class "Default")
      (node (ref "A26") (pin "1") (pinfunction "CLR_1") (pintype "input"))
      (node (ref "A37") (pin "3") (pinfunction "O_3") (pintype "output"))
    )
    (net (code "207") (name "Net-(A26A-D)") (class "Default")
      (node (ref "A26") (pin "2") (pinfunction "D_2") (pintype "input"))
      (node (ref "A40") (pin "6") (pinfunction "O_6") (pintype "output"))
    )
    (net (code "208") (name "Net-(A29B-O)") (class "Default")
      (node (ref "A29") (pin "6") (pinfunction "O_6") (pintype "output"))
      (node (ref "A47") (pin "13") (pinfunction "I_13") (pintype "input"))
    )
    (net (code "209") (name "Net-(A30B-D)") (class "Default")
      (node (ref "A30") (pin "12") (pinfunction "D_12") (pintype "input"))
      (node (ref "A48") (pin "8") (pinfunction "O_8") (pintype "output"))
    )
    (net (code "210") (name "Net-(A30B-~{Q})") (class "Default")
      (node (ref "A30") (pin "8") (pinfunction "~{Q}_8") (pintype "output"))
      (node (ref "A40") (pin "5") (pinfunction "I2_5") (pintype "input"))
    )
    (net (code "211") (name "Net-(A31A-CLR)") (class "Default")
      (node (ref "A31") (pin "1") (pinfunction "CLR_1") (pintype "input"))
      (node (ref "CCJ1") (pin "23") (pinfunction "S_23") (pintype "passive"))
    )
    (net (code "212") (name "Net-(A31A-~{Q})") (class "Default")
      (node (ref "A31") (pin "6") (pinfunction "~{Q}_6") (pintype "output"))
      (node (ref "CCJ1") (pin "25") (pinfunction "S_25") (pintype "passive"))
    )
    (net (code "213") (name "Net-(A31B-D)") (class "Default")
      (node (ref "A31") (pin "12") (pinfunction "D_12") (pintype "input"))
      (node (ref "A41") (pin "6") (pinfunction "O_6") (pintype "output"))
    )
    (net (code "214") (name "Net-(A34A-I0)") (class "Default")
      (node (ref "A34") (pin "2") (pinfunction "I0_2") (pintype "input"))
      (node (ref "A36") (pin "8") (pinfunction "O_8") (pintype "output"))
    )
    (net (code "215") (name "Net-(A35A-I0)") (class "Default")
      (node (ref "A35") (pin "2") (pinfunction "I0_2") (pintype "input"))
      (node (ref "A45") (pin "8") (pinfunction "O_8") (pintype "output"))
    )
    (net (code "216") (name "Net-(A35B-I1)") (class "Default")
      (node (ref "A35") (pin "6") (pinfunction "I1_6") (pintype "input"))
      (node (ref "A45") (pin "2") (pinfunction "O_2") (pintype "output"))
    )
    (net (code "217") (name "Net-(A35C-I0)") (class "Default")
      (node (ref "A35") (pin "8") (pinfunction "I0_8") (pintype "input"))
      (node (ref "A45") (pin "6") (pinfunction "O_6") (pintype "output"))
    )
    (net (code "218") (name "Net-(A35D-I1)") (class "Default")
      (node (ref "A35") (pin "12") (pinfunction "I1_12") (pintype "input"))
      (node (ref "A45") (pin "4") (pinfunction "O_4") (pintype "output"))
    )
    (net (code "219") (name "Net-(A36A-O)") (class "Default")
      (node (ref "A36") (pin "3") (pinfunction "O_3") (pintype "output"))
      (node (ref "A37") (pin "1") (pinfunction "I0_1") (pintype "input"))
    )
    (net (code "220") (name "Net-(A36B-I0)") (class "Default")
      (node (ref "A36") (pin "4") (pinfunction "I0_4") (pintype "input"))
      (node (ref "A46") (pin "10") (pinfunction "O_10") (pintype "output"))
    )
    (net (code "221") (name "Net-(A36B-O)") (class "Default")
      (node (ref "A36") (pin "6") (pinfunction "O_6") (pintype "output"))
      (node (ref "A36") (pin "9") (pinfunction "I0_9") (pintype "input"))
    )
    (net (code "222") (name "Net-(A36C-I1)") (class "Default")
      (node (ref "A36") (pin "10") (pinfunction "I1_10") (pintype "input"))
      (node (ref "A36") (pin "11") (pinfunction "O_11") (pintype "output"))
    )
    (net (code "223") (name "Net-(A36D-I1)") (class "Default")
      (node (ref "A36") (pin "13") (pinfunction "I1_13") (pintype "input"))
      (node (ref "A37") (pin "4") (pinfunction "I0_4") (pintype "input"))
      (node (ref "A37") (pin "5") (pinfunction "I1_5") (pintype "input"))
      (node (ref "A38") (pin "10") (pinfunction "O_10") (pintype "output"))
    )
    (net (code "224") (name "Net-(A38A-O)") (class "Default")
      (node (ref "A38") (pin "2") (pinfunction "O_2") (pintype "output"))
      (node (ref "A39") (pin "6") (pinfunction "I1_6") (pintype "input"))
    )
    (net (code "225") (name "Net-(A38B-O)") (class "Default")
      (node (ref "A38") (pin "4") (pinfunction "O_4") (pintype "output"))
      (node (ref "A39") (pin "12") (pinfunction "I1_12") (pintype "input"))
    )
    (net (code "226") (name "Net-(A38C-O)") (class "Default")
      (node (ref "A38") (pin "6") (pinfunction "O_6") (pintype "output"))
      (node (ref "A39") (pin "8") (pinfunction "I0_8") (pintype "input"))
    )
    (net (code "227") (name "Net-(A38F-O)") (class "Default")
      (node (ref "A38") (pin "12") (pinfunction "O_12") (pintype "output"))
      (node (ref "A39") (pin "2") (pinfunction "I0_2") (pintype "input"))
    )
    (net (code "228") (name "Net-(A40A-O)") (class "Default")
      (node (ref "A40") (pin "12") (pinfunction "O_12") (pintype "output"))
      (node (ref "A48") (pin "1") (pinfunction "I_1") (pintype "input"))
    )
    (net (code "229") (name "Net-(A40B-I0)") (class "Default")
      (node (ref "A40") (pin "3") (pinfunction "I0_3") (pintype "input"))
      (node (ref "A48") (pin "9") (pinfunction "I_9") (pintype "input"))
      (node (ref "A49") (pin "8") (pinfunction "O_8") (pintype "open_collector"))
      (node (ref "R11") (pin "1") (pinfunction "1_1") (pintype "passive"))
    )
    (net (code "230") (name "Net-(A40C-O)") (class "Default")
      (node (ref "A40") (pin "8") (pinfunction "O_8") (pintype "output"))
      (node (ref "A49") (pin "12") (pinfunction "I0_12") (pintype "input"))
    )
    (net (code "231") (name "Net-(A42C-O)") (class "Default")
      (node (ref "A42") (pin "10") (pinfunction "O_10") (pintype "output"))
      (node (ref "A49") (pin "9") (pinfunction "I0_9") (pintype "input"))
    )
    (net (code "232") (name "Net-(A43A-O)") (class "Default")
      (node (ref "A43") (pin "2") (pinfunction "O_2") (pintype "output"))
      (node (ref "A44") (pin "6") (pinfunction "I1_6") (pintype "input"))
    )
    (net (code "233") (name "Net-(A43B-O)") (class "Default")
      (node (ref "A43") (pin "4") (pinfunction "O_4") (pintype "output"))
      (node (ref "A44") (pin "12") (pinfunction "I1_12") (pintype "input"))
    )
    (net (code "234") (name "Net-(A43C-O)") (class "Default")
      (node (ref "A43") (pin "6") (pinfunction "O_6") (pintype "output"))
      (node (ref "A44") (pin "8") (pinfunction "I0_8") (pintype "input"))
    )
    (net (code "235") (name "Net-(A43F-O)") (class "Default")
      (node (ref "A43") (pin "12") (pinfunction "O_12") (pintype "output"))
      (node (ref "A44") (pin "2") (pinfunction "I0_2") (pintype "input"))
    )
    (net (code "236") (name "Net-(A46A-I)") (class "Default")
      (node (ref "A46") (pin "1") (pinfunction "I_1") (pintype "input"))
      (node (ref "A53") (pin "7") (pinfunction "TERM_7") (pintype "input"))
      (node (ref "CCJ1") (pin "15") (pinfunction "S_15") (pintype "passive"))
    )
    (net (code "237") (name "Net-(A46A-O)") (class "Default")
      (node (ref "A46") (pin "2") (pinfunction "O_2") (pintype "output"))
      (node (ref "A49") (pin "10") (pinfunction "I1_10") (pintype "input"))
    )
    (net (code "238") (name "Net-(A48A-O)") (class "Default")
      (node (ref "A48") (pin "2") (pinfunction "O_2") (pintype "output"))
      (node (ref "A57") (pin "9") (pinfunction "I_9") (pintype "input"))
    )
    (net (code "239") (name "Net-(A48B-O)") (class "Default")
      (node (ref "A48") (pin "4") (pinfunction "O_4") (pintype "output"))
      (node (ref "A57") (pin "11") (pinfunction "I_11") (pintype "input"))
    )
    (net (code "240") (name "Net-(A48C-I)") (class "Default")
      (node (ref "A48") (pin "5") (pinfunction "I_5") (pintype "input"))
      (node (ref "A56") (pin "8") (pinfunction "O_8") (pintype "output"))
      (node (ref "A8") (pin "3") (pinfunction "I1_3") (pintype "input"))
    )
    (net (code "241") (name "Net-(A49A-O)") (class "Default")
      (node (ref "A49") (pin "3") (pinfunction "O_3") (pintype "open_collector"))
      (node (ref "CDJ2") (pin "13") (pinfunction "S_13") (pintype "passive"))
    )
    (net (code "242") (name "Net-(A49D-O)") (class "Default")
      (node (ref "A49") (pin "11") (pinfunction "O_11") (pintype "open_collector"))
      (node (ref "A55") (pin "12") (pinfunction "I0_12") (pintype "input"))
    )
    (net (code "243") (name "Net-(A51E-O)") (class "Default")
      (node (ref "A51") (pin "10") (pinfunction "O_10") (pintype "open_collector"))
      (node (ref "CDJ2") (pin "9") (pinfunction "S_9") (pintype "passive"))
    )
    (net (code "244") (name "Net-(A51F-O)") (class "Default")
      (node (ref "A51") (pin "12") (pinfunction "O_12") (pintype "open_collector"))
      (node (ref "CDJ2") (pin "11") (pinfunction "S_11") (pintype "passive"))
    )
    (net (code "245") (name "Net-(A55A-O)") (class "Default")
      (node (ref "A55") (pin "3") (pinfunction "O_3") (pintype "output"))
      (node (ref "A8") (pin "12") (pinfunction "I1_12") (pintype "input"))
    )
    (net (code "246") (name "Net-(A55C-I1)") (class "Default")
      (node (ref "A55") (pin "10") (pinfunction "I1_10") (pintype "input"))
      (node (ref "R12") (pin "1") (pinfunction "1_1") (pintype "passive"))
    )
    (net (code "247") (name "Net-(A56A-O)") (class "Default")
      (node (ref "A56") (pin "11") (pinfunction "I2_11") (pintype "input"))
      (node (ref "A56") (pin "12") (pinfunction "O_12") (pintype "output"))
    )
    (net (code "248") (name "Net-(A56B-O)") (class "Default")
      (node (ref "A56") (pin "10") (pinfunction "I1_10") (pintype "input"))
      (node (ref "A56") (pin "6") (pinfunction "O_6") (pintype "output"))
      (node (ref "A56") (pin "9") (pinfunction "I0_9") (pintype "input"))
    )
    (net (code "249") (name "Net-(A57A-O)") (class "Default")
      (node (ref "A57") (pin "2") (pinfunction "O_2") (pintype "open_collector"))
      (node (ref "CDJ2") (pin "25") (pinfunction "S_25") (pintype "passive"))
    )
    (net (code "250") (name "Net-(A57B-O)") (class "Default")
      (node (ref "A57") (pin "4") (pinfunction "O_4") (pintype "open_collector"))
      (node (ref "CDJ2") (pin "23") (pinfunction "S_23") (pintype "passive"))
    )
    (net (code "251") (name "Net-(A57C-O)") (class "Default")
      (node (ref "A57") (pin "6") (pinfunction "O_6") (pintype "open_collector"))
      (node (ref "CDJ2") (pin "21") (pinfunction "S_21") (pintype "passive"))
    )
    (net (code "252") (name "Net-(A57D-O)") (class "Default")
      (node (ref "A57") (pin "8") (pinfunction "O_8") (pintype "open_collector"))
      (node (ref "CDJ2") (pin "15") (pinfunction "S_15") (pintype "passive"))
    )
    (net (code "253") (name "Net-(A57E-O)") (class "Default")
      (node (ref "A57") (pin "10") (pinfunction "O_10") (pintype "open_collector"))
      (node (ref "CDJ2") (pin "17") (pinfunction "S_17") (pintype "passive"))
    )
    (net (code "254") (name "Net-(A57F-O)") (class "Default")
      (node (ref "A57") (pin "12") (pinfunction "O_12") (pintype "open_collector"))
      (node (ref "CDJ2") (pin "19") (pinfunction "S_19") (pintype "passive"))
    )
    (net (code "255") (name "Net-(CCJ1N-S)") (class "Default")
      (node (ref "CCJ1") (pin "21") (pinfunction "S_21") (pintype "passive"))
      (node (ref "R10") (pin "1") (pinfunction "1_1") (pintype "passive"))
    )
    (net (code "256") (name "VCC") (class "Default")
      (node (ref "C1") (pin "1") (pinfunction "1_1") (pintype "passive"))
      (node (ref "C10") (pin "1") (pinfunction "1_1") (pintype "passive"))
      (node (ref "C11") (pin "1") (pinfunction "1_1") (pintype "passive"))
      (node (ref "C12") (pin "1") (pinfunction "1_1") (pintype "passive"))
      (node (ref "C13") (pin "1") (pinfunction "1_1") (pintype "passive"))
      (node (ref "C14") (pin "1") (pinfunction "1_1") (pintype "passive"))
      (node (ref "C15") (pin "1") (pinfunction "1_1") (pintype "passive"))
      (node (ref "C16") (pin "1") (pinfunction "1_1") (pintype "passive"))
      (node (ref "C17") (pin "1") (pinfunction "1_1") (pintype "passive"))
      (node (ref "C18") (pin "1") (pinfunction "1_1") (pintype "passive"))
      (node (ref "C19") (pin "1") (pinfunction "1_1") (pintype "passive"))
      (node (ref "C2") (pin "1") (pinfunction "1_1") (pintype "passive"))
      (node (ref "C20") (pin "1") (pinfunction "1_1") (pintype "passive"))
      (node (ref "C21") (pin "1") (pinfunction "1_1") (pintype "passive"))
      (node (ref "C22") (pin "1") (pinfunction "1_1") (pintype "passive"))
      (node (ref "C23") (pin "1") (pinfunction "1_1") (pintype "passive"))
      (node (ref "C24") (pin "1") (pinfunction "1_1") (pintype "passive"))
      (node (ref "C25") (pin "1") (pinfunction "1_1") (pintype "passive"))
      (node (ref "C26") (pin "1") (pinfunction "1_1") (pintype "passive"))
      (node (ref "C3") (pin "1") (pinfunction "1_1") (pintype "passive"))
      (node (ref "C4") (pin "1") (pinfunction "1_1") (pintype "passive"))
      (node (ref "C5") (pin "1") (pinfunction "1_1") (pintype "passive"))
      (node (ref "C6") (pin "1") (pinfunction "1_1") (pintype "passive"))
      (node (ref "C7") (pin "1") (pinfunction "1_1") (pintype "passive"))
      (node (ref "C8") (pin "1") (pinfunction "1_1") (pintype "passive"))
      (node (ref "C9") (pin "1") (pinfunction "1_1") (pintype "passive"))
      (node (ref "R1") (pin "1") (pinfunction "1_1") (pintype "passive"))
      (node (ref "R10") (pin "2") (pinfunction "2_2") (pintype "passive"))
      (node (ref "R11") (pin "2") (pinfunction "2_2") (pintype "passive"))
      (node (ref "R12") (pin "2") (pinfunction "2_2") (pintype "passive"))
      (node (ref "R2") (pin "2") (pinfunction "2_2") (pintype "passive"))
      (node (ref "R3") (pin "2") (pinfunction "2_2") (pintype "passive"))
      (node (ref "R4") (pin "2") (pinfunction "2_2") (pintype "passive"))
      (node (ref "R5") (pin "2") (pinfunction "2_2") (pintype "passive"))
      (node (ref "R6") (pin "2") (pinfunction "2_2") (pintype "passive"))
      (node (ref "R7") (pin "2") (pinfunction "2_2") (pintype "passive"))
      (node (ref "R8") (pin "2") (pinfunction "2_2") (pintype "passive"))
      (node (ref "R9") (pin "2") (pinfunction "2_2") (pintype "passive"))
      (node (ref "U$2") (pin "AA2") (pinfunction "1_AA2") (pintype "bidirectional"))
      (node (ref "U$2") (pin "BA2") (pinfunction "1_BA2") (pintype "bidirectional"))
      (node (ref "U$2") (pin "CA2") (pinfunction "1_CA2") (pintype "bidirectional"))
    )
    (net (code "257") (name "unconnected-(A7A-I1-Pad5)") (class "Default")
      (node (ref "A7") (pin "5") (pinfunction "I1_5") (pintype "input"))
    )
    (net (code "258") (name "unconnected-(A7A-O-Pad3)") (class "Default")
      (node (ref "A7") (pin "3") (pinfunction "O_3") (pintype "output"))
    )
    (net (code "259") (name "unconnected-(A13A-~{QD}-Pad11)") (class "Default")
      (node (ref "A13") (pin "11") (pinfunction "~{QD}_11") (pintype "output"))
    )
    (net (code "260") (name "unconnected-(A14A-G-Pad3)") (class "Default")
      (node (ref "A14") (pin "3") (pinfunction "G_3") (pintype "input"))
    )
    (net (code "261") (name "unconnected-(A14A-I0-Pad1)") (class "Default")
      (node (ref "A14") (pin "1") (pinfunction "I0_1") (pintype "input"))
    )
    (net (code "262") (name "unconnected-(A14A-I1-Pad2)") (class "Default")
      (node (ref "A14") (pin "2") (pinfunction "I1_2") (pintype "input"))
    )
    (net (code "263") (name "unconnected-(A14A-I2-Pad4)") (class "Default")
      (node (ref "A14") (pin "4") (pinfunction "I2_4") (pintype "input"))
    )
    (net (code "264") (name "unconnected-(A14A-O-Pad6)") (class "Default")
      (node (ref "A14") (pin "6") (pinfunction "O_6") (pintype "output"))
    )
    (net (code "265") (name "unconnected-(A15A-~{Q}-Pad6)") (class "Default")
      (node (ref "A15") (pin "6") (pinfunction "~{Q}_6") (pintype "output"))
    )
    (net (code "266") (name "unconnected-(A15B-~{Q}-Pad8)") (class "Default")
      (node (ref "A15") (pin "8") (pinfunction "~{Q}_8") (pintype "output"))
    )
    (net (code "267") (name "unconnected-(A17A-~{QD}-Pad11)") (class "Default")
      (node (ref "A17") (pin "11") (pinfunction "~{QD}_11") (pintype "output"))
    )
    (net (code "268") (name "unconnected-(A22A-~{QD}-Pad11)") (class "Default")
      (node (ref "A22") (pin "11") (pinfunction "~{QD}_11") (pintype "output"))
    )
    (net (code "269") (name "unconnected-(A26A-~{Q}-Pad6)") (class "Default")
      (node (ref "A26") (pin "6") (pinfunction "~{Q}_6") (pintype "output"))
    )
    (net (code "270") (name "unconnected-(A26B-~{Q}-Pad8)") (class "Default")
      (node (ref "A26") (pin "8") (pinfunction "~{Q}_8") (pintype "output"))
    )
    (net (code "271") (name "unconnected-(A31A-CLK-Pad3)") (class "Default")
      (node (ref "A31") (pin "3") (pinfunction "CLK_3") (pintype "input"))
    )
    (net (code "272") (name "unconnected-(A31A-D-Pad2)") (class "Default")
      (node (ref "A31") (pin "2") (pinfunction "D_2") (pintype "input"))
    )
    (net (code "273") (name "unconnected-(A31A-Q-Pad5)") (class "Default")
      (node (ref "A31") (pin "5") (pinfunction "Q_5") (pintype "output"))
    )
  )
)
